# TH8_Supply.net
KiCad netlist of a schematic drawn in Altium Designer
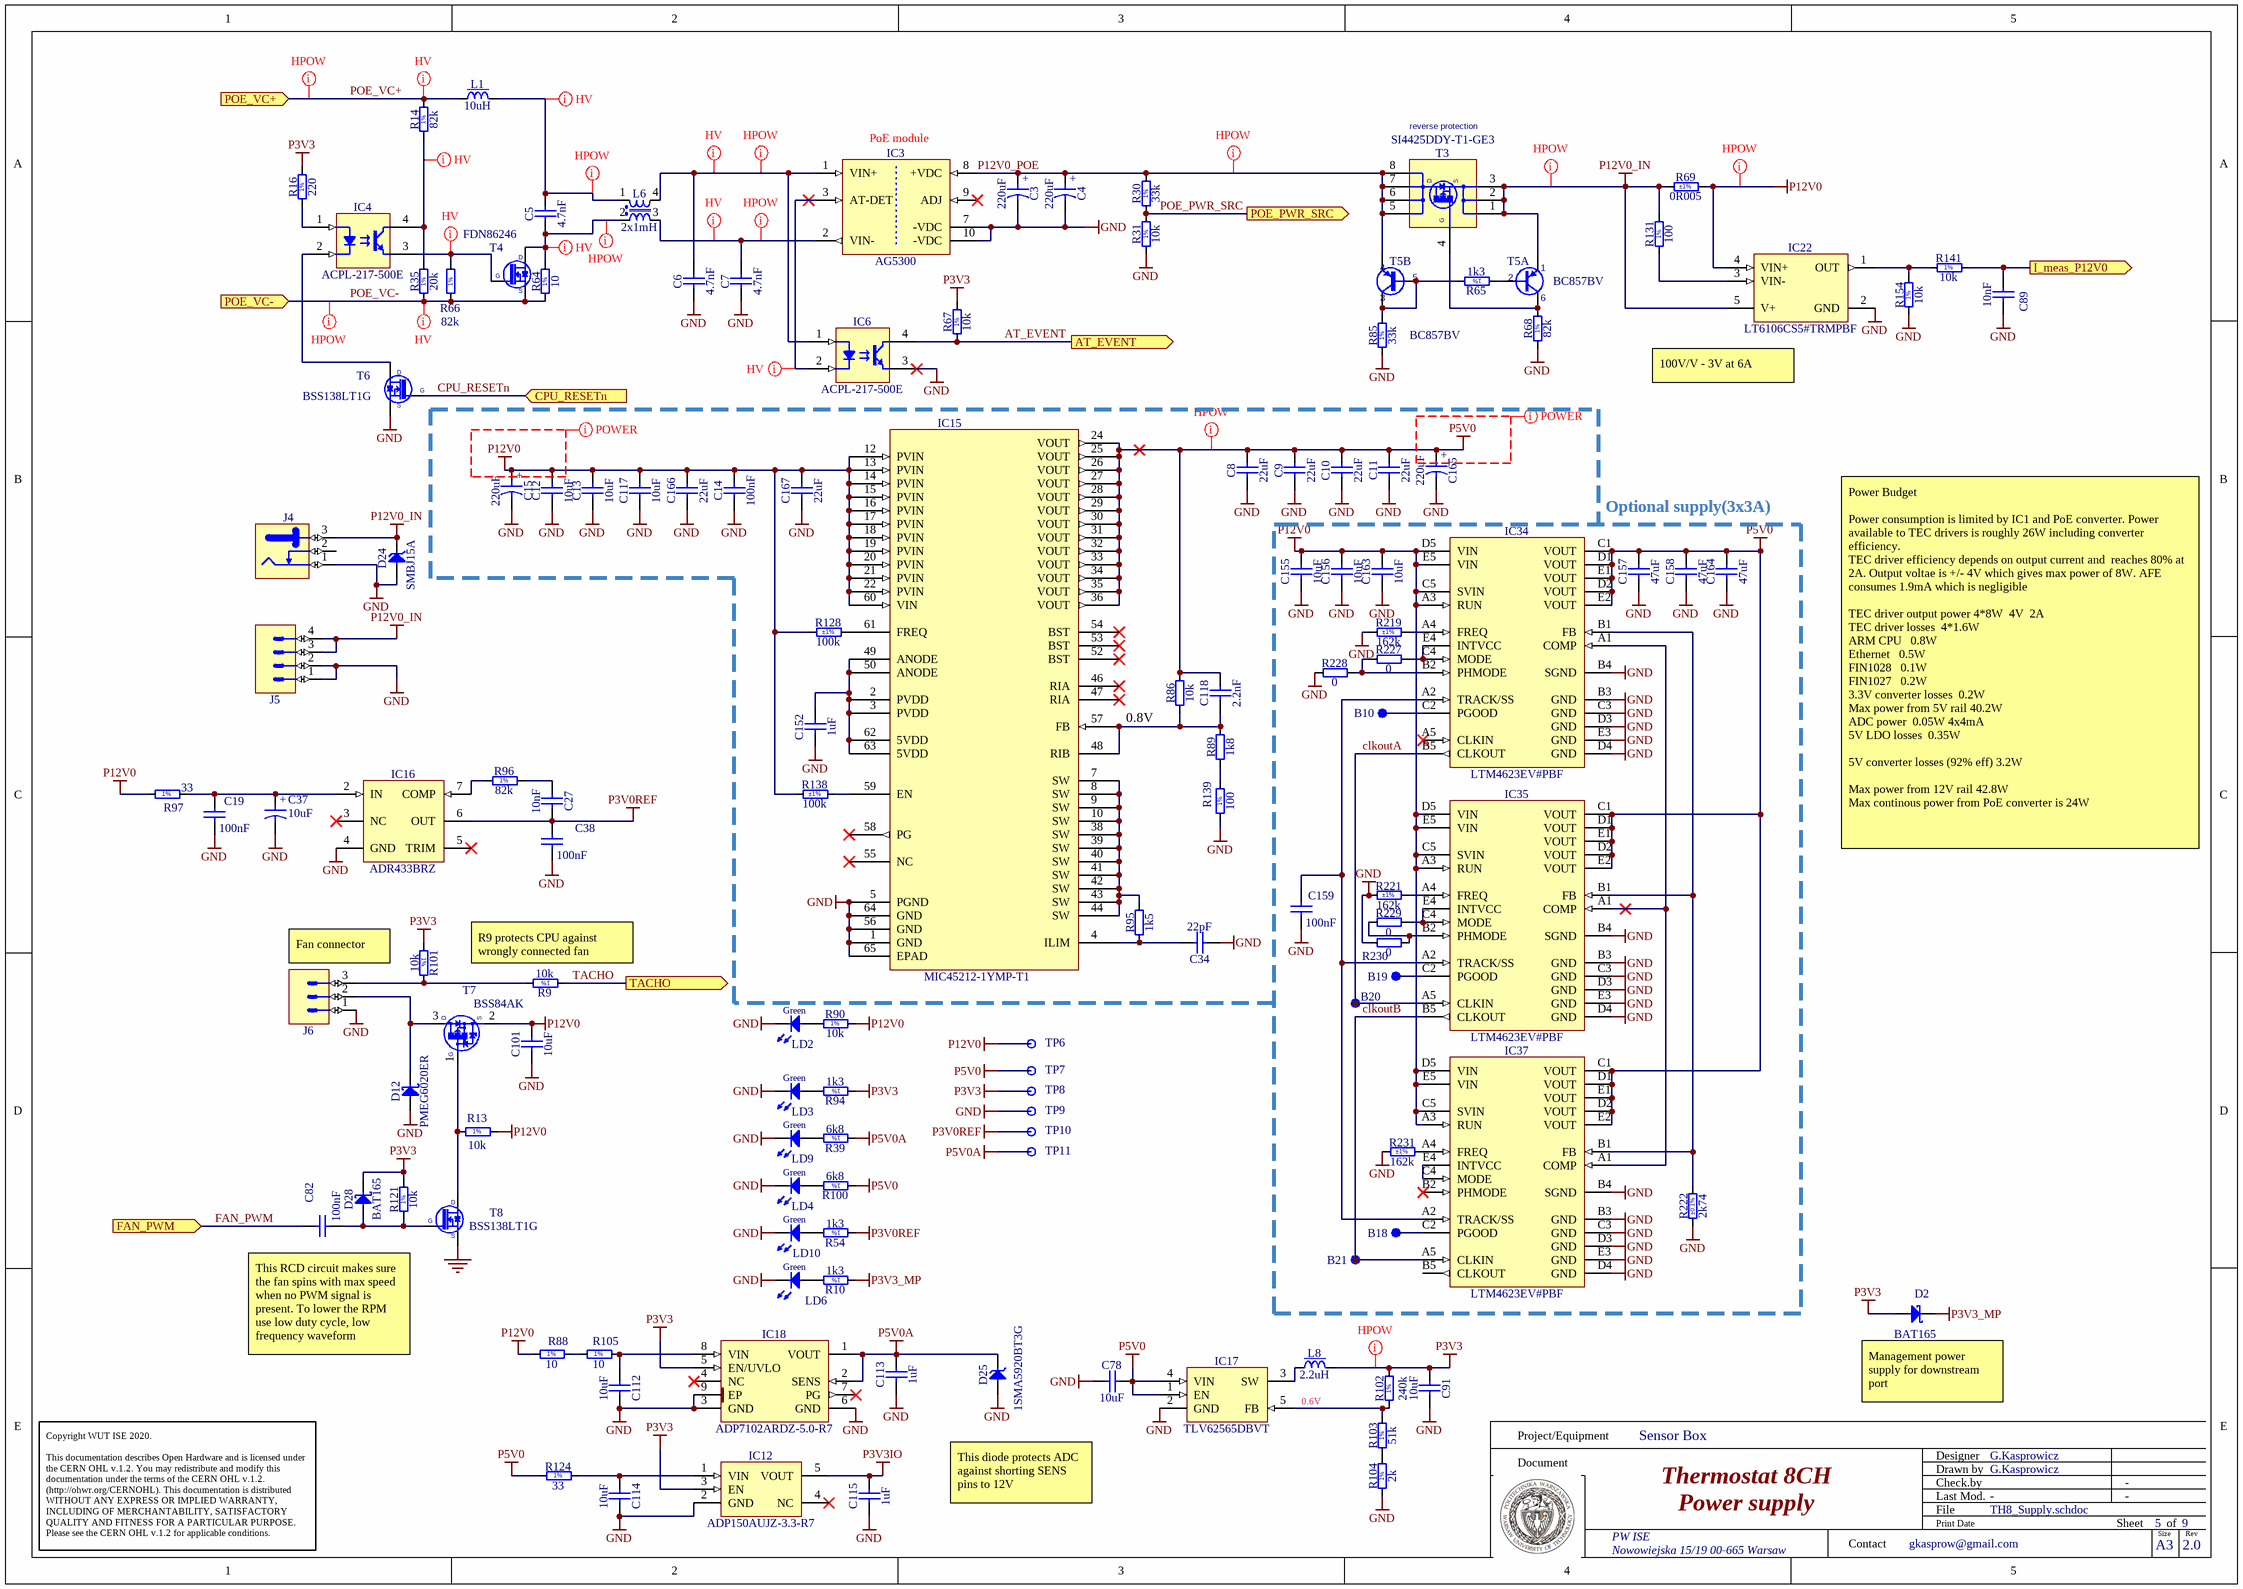
[diagram p0: TH8_Supply.schdoc]

(export (version "E")
  (design (tool "Eeschema 10.0.6"))
  (components
    (comp (ref "B10")
      (value "SMD Pad")
      (footprint "C75")
      (description "Through Hole Pad")
      (fields (field (name "PART NUMBER") "SMD_PAD_D0.75MM") (field (name "AUTHOR") "CERN DEM BC"))
      (libsource (lib "Eletro-mechanical") (part "Single SMD Pad (Round)"))
    )
    (comp (ref "B18")
      (value "SMD Pad")
      (footprint "C75")
      (description "Through Hole Pad")
      (fields (field (name "PART NUMBER") "SMD_PAD_D0.75MM") (field (name "AUTHOR") "CERN DEM BC"))
      (libsource (lib "Eletro-mechanical") (part "Single SMD Pad (Round)"))
    )
    (comp (ref "B19")
      (value "SMD Pad")
      (footprint "C75")
      (description "Through Hole Pad")
      (fields (field (name "PART NUMBER") "SMD_PAD_D0.75MM") (field (name "AUTHOR") "CERN DEM BC"))
      (libsource (lib "Eletro-mechanical") (part "Single SMD Pad (Round)"))
    )
    (comp (ref "B20")
      (value "SMD Pad")
      (footprint "C75")
      (description "Through Hole Pad")
      (fields (field (name "PART NUMBER") "SMD_PAD_D0.75MM") (field (name "AUTHOR") "CERN DEM BC"))
      (libsource (lib "Eletro-mechanical") (part "Single SMD Pad (Round)"))
    )
    (comp (ref "B21")
      (value "SMD Pad")
      (footprint "C75")
      (description "Through Hole Pad")
      (fields (field (name "PART NUMBER") "SMD_PAD_D0.75MM") (field (name "AUTHOR") "CERN DEM BC"))
      (libsource (lib "Eletro-mechanical") (part "Single SMD Pad (Round)"))
    )
    (comp (ref "C3")
      (value "220uF")
      (footprint "CAPMP7343X430N")
      (description "Polarised capacitor")
      (fields
        (field (name "PART NUMBER") "CTE7343-43_220UF_16V_10%")
        (field (name "VOLTAGE") "16V")
        (field (name "AUTHOR") "CERN DEM JLC")
      )
      (libsource (lib "Capacitors") (part "Capacitor - polarized"))
    )
    (comp (ref "C4")
      (value "220uF")
      (footprint "CAPMP7343X430N")
      (description "Polarised capacitor")
      (fields
        (field (name "PART NUMBER") "CTE7343-43_220UF_16V_10%")
        (field (name "VOLTAGE") "16V")
        (field (name "AUTHOR") "CERN DEM JLC")
      )
      (libsource (lib "Capacitors") (part "Capacitor - polarized"))
    )
    (comp (ref "C5")
      (value "4.7nF")
      (footprint "CAPC3216X140N")
      (description "Non-polarised capacitor")
      (fields
        (field (name "PART NUMBER") "CC1206_4.7NF_500V_10%_X7R")
        (field (name "VOLTAGE") "500V")
        (field (name "AUTHOR") "GK")
      )
      (libsource (lib "LIBRARY_SCH") (part "CAP_SMD_1206_4.7n_500V"))
    )
    (comp (ref "C6")
      (value "4.7nF")
      (footprint "CAPC3216X140N")
      (description "Non-polarised capacitor")
      (fields
        (field (name "PART NUMBER") "CC1206_4.7NF_500V_10%_X7R")
        (field (name "VOLTAGE") "500V")
        (field (name "AUTHOR") "GK")
      )
      (libsource (lib "LIBRARY_SCH") (part "CAP_SMD_1206_4.7n_500V"))
    )
    (comp (ref "C7")
      (value "4.7nF")
      (footprint "CAPC3216X140N")
      (description "Non-polarised capacitor")
      (fields
        (field (name "PART NUMBER") "CC1206_4.7NF_500V_10%_X7R")
        (field (name "VOLTAGE") "500V")
        (field (name "AUTHOR") "GK")
      )
      (libsource (lib "LIBRARY_SCH") (part "CAP_SMD_1206_4.7n_500V"))
    )
    (comp (ref "C8")
      (value "22uF")
      (footprint "CAPC2012X135N")
      (description "Non-polarised capacitor")
      (fields
        (field (name "PART NUMBER") "CC0805_22UF_16V_10%_X5R")
        (field (name "VOLTAGE") "16V")
        (field (name "AUTHOR") "CERN DEM JLC")
      )
      (libsource (lib "Capacitors") (part "Capacitor - non polarized"))
    )
    (comp (ref "C9")
      (value "22uF")
      (footprint "CAPC2012X135N")
      (description "Non-polarised capacitor")
      (fields
        (field (name "PART NUMBER") "CC0805_22UF_16V_10%_X5R")
        (field (name "VOLTAGE") "16V")
        (field (name "AUTHOR") "CERN DEM JLC")
      )
      (libsource (lib "Capacitors") (part "Capacitor - non polarized"))
    )
    (comp (ref "C10")
      (value "22uF")
      (footprint "CAPC2012X135N")
      (description "Non-polarised capacitor")
      (fields
        (field (name "PART NUMBER") "CC0805_22UF_16V_10%_X5R")
        (field (name "VOLTAGE") "16V")
        (field (name "AUTHOR") "CERN DEM JLC")
      )
      (libsource (lib "Capacitors") (part "Capacitor - non polarized"))
    )
    (comp (ref "C11")
      (value "22uF")
      (footprint "CAPC2012X135N")
      (description "Non-polarised capacitor")
      (fields
        (field (name "PART NUMBER") "CC0805_22UF_16V_10%_X5R")
        (field (name "VOLTAGE") "16V")
        (field (name "AUTHOR") "CERN DEM JLC")
      )
      (libsource (lib "Capacitors") (part "Capacitor - non polarized"))
    )
    (comp (ref "C12")
      (value "10uF")
      (footprint "CAPC2012X135N")
      (description "Non-polarised capacitor")
      (fields
        (field (name "PART NUMBER") "CC0805_10UF_16V_10%_X5R")
        (field (name "VOLTAGE") "16V")
        (field (name "AUTHOR") "CERN DEM JLC")
      )
      (libsource (lib "Capacitors") (part "Capacitor - non polarized"))
    )
    (comp (ref "C13")
      (value "10uF")
      (footprint "CAPC2012X135N")
      (description "Non-polarised capacitor")
      (fields
        (field (name "PART NUMBER") "CC0805_10UF_16V_10%_X5R")
        (field (name "VOLTAGE") "16V")
        (field (name "AUTHOR") "CERN DEM JLC")
      )
      (libsource (lib "Capacitors") (part "Capacitor - non polarized"))
    )
    (comp (ref "C14")
      (value "100nF")
      (footprint "CAPC1005X55N")
      (description "Non-polarised capacitor")
      (fields
        (field (name "PART NUMBER") "CC0402_100NF_16V_10%_X5R")
        (field (name "VOLTAGE") "16V")
        (field (name "AUTHOR") "CERN DEM JLC")
      )
      (libsource (lib "Capacitors") (part "Capacitor - non polarized"))
    )
    (comp (ref "C15")
      (value "220uF")
      (footprint "CAPMP7343X430N")
      (description "Polarised capacitor")
      (fields
        (field (name "PART NUMBER") "CTE7343-43_220UF_16V_10%")
        (field (name "VOLTAGE") "16V")
        (field (name "AUTHOR") "CERN DEM JLC")
      )
      (libsource (lib "Capacitors") (part "Capacitor - polarized"))
    )
    (comp (ref "C19")
      (value "100nF")
      (footprint "CAPC1005X55N")
      (description "Non-polarised capacitor")
      (fields
        (field (name "PART NUMBER") "CC0402_100NF_16V_10%_X5R")
        (field (name "VOLTAGE") "16V")
        (field (name "AUTHOR") "CERN DEM JLC")
      )
      (libsource (lib "Capacitors") (part "Capacitor - non polarized"))
    )
    (comp (ref "C27")
      (value "10nF")
      (footprint "CAPC1005X55N")
      (description "Non-polarised capacitor")
      (fields
        (field (name "PART NUMBER") "CC0402_10NF_16V_10%_X7R")
        (field (name "VOLTAGE") "16V")
        (field (name "AUTHOR") "CERN DEM JLC")
      )
      (libsource (lib "Capacitors") (part "Capacitor - non polarized"))
    )
    (comp (ref "C34")
      (value "22pF")
      (footprint "CAPC1005X55N")
      (description "Non-polarised capacitor")
      (fields
        (field (name "PART NUMBER") "CC0402_22PF_50V_5%_C0G")
        (field (name "VOLTAGE") "50V")
        (field (name "AUTHOR") "CERN DEM JLC")
      )
      (libsource (lib "Capacitors") (part "Capacitor - non polarized"))
    )
    (comp (ref "C37")
      (value "10uF")
      (footprint "CAPMP3216X180N")
      (description "Polarised capacitor")
      (fields
        (field (name "PART NUMBER") "CTE3216-18_10UF_16V_20%_AVX_TCJ")
        (field (name "VOLTAGE") "16V")
        (field (name "AUTHOR") "CERN DEM JLC")
      )
      (libsource (lib "Capacitors") (part "Capacitor - polarized"))
    )
    (comp (ref "C38")
      (value "100nF")
      (footprint "CAPC1005X55N")
      (description "Non-polarised capacitor")
      (fields
        (field (name "PART NUMBER") "CC0402_100NF_16V_10%_X5R")
        (field (name "VOLTAGE") "16V")
        (field (name "AUTHOR") "CERN DEM JLC")
      )
      (libsource (lib "Capacitors") (part "Capacitor - non polarized"))
    )
    (comp (ref "C78")
      (value "10uF")
      (footprint "CAPC2012X135N")
      (description "Non-polarised capacitor")
      (fields
        (field (name "PART NUMBER") "CC0805_10UF_16V_10%_X5R")
        (field (name "VOLTAGE") "16V")
        (field (name "AUTHOR") "CERN DEM JLC")
      )
      (libsource (lib "Capacitors") (part "Capacitor - non polarized"))
    )
    (comp (ref "C82")
      (value "100nF")
      (footprint "CAPC1005X55N")
      (description "Non-polarised capacitor")
      (fields
        (field (name "PART NUMBER") "CC0402_100NF_16V_10%_X5R")
        (field (name "VOLTAGE") "16V")
        (field (name "AUTHOR") "CERN DEM JLC")
      )
      (libsource (lib "Capacitors") (part "Capacitor - non polarized"))
    )
    (comp (ref "C89")
      (value "10nF")
      (footprint "CAPC1005X55N")
      (description "Non-polarised capacitor")
      (fields
        (field (name "PART NUMBER") "CC0402_10NF_25V_10%_X7R")
        (field (name "VOLTAGE") "25V")
        (field (name "AUTHOR") "CERN DEM JLC")
      )
      (libsource (lib "Capacitors") (part "Capacitor - non polarized"))
    )
    (comp (ref "C91")
      (value "10uF")
      (footprint "CAPC2012X135N")
      (description "Non-polarised capacitor")
      (fields
        (field (name "PART NUMBER") "CC0805_10UF_16V_10%_X5R")
        (field (name "VOLTAGE") "16V")
        (field (name "AUTHOR") "CERN DEM JLC")
      )
      (libsource (lib "Capacitors") (part "Capacitor - non polarized"))
    )
    (comp (ref "C101")
      (value "10uF")
      (footprint "CAPC2012X135N")
      (description "Non-polarised capacitor")
      (fields
        (field (name "PART NUMBER") "CC0805_10UF_16V_10%_X5R")
        (field (name "VOLTAGE") "16V")
        (field (name "AUTHOR") "CERN DEM JLC")
      )
      (libsource (lib "Capacitors") (part "Capacitor - non polarized"))
    )
    (comp (ref "C112")
      (value "10uF")
      (footprint "CAPC2012X135N")
      (description "Non-polarised capacitor")
      (fields
        (field (name "PART NUMBER") "CC0805_10UF_16V_10%_X5R")
        (field (name "VOLTAGE") "16V")
        (field (name "AUTHOR") "CERN DEM JLC")
      )
      (libsource (lib "Capacitors") (part "Capacitor - non polarized"))
    )
    (comp (ref "C113")
      (value "1uF")
      (footprint "CAPC1608X87N")
      (description "Non-polarised capacitor")
      (fields
        (field (name "PART NUMBER") "CC0603_1UF_25V_10%_X7R")
        (field (name "VOLTAGE") "25V")
        (field (name "AUTHOR") "CERN DEM JLC")
      )
      (libsource (lib "Capacitors") (part "Capacitor - non polarized"))
    )
    (comp (ref "C114")
      (value "10uF")
      (footprint "CAPC2012X135N")
      (description "Non-polarised capacitor")
      (fields
        (field (name "PART NUMBER") "CC0805_10UF_16V_10%_X5R")
        (field (name "VOLTAGE") "16V")
        (field (name "AUTHOR") "CERN DEM JLC")
      )
      (libsource (lib "Capacitors") (part "Capacitor - non polarized"))
    )
    (comp (ref "C115")
      (value "1uF")
      (footprint "CAPC1608X87N")
      (description "Non-polarised capacitor")
      (fields
        (field (name "PART NUMBER") "CC0603_1UF_25V_10%_X7R")
        (field (name "VOLTAGE") "25V")
        (field (name "AUTHOR") "CERN DEM JLC")
      )
      (libsource (lib "Capacitors") (part "Capacitor - non polarized"))
    )
    (comp (ref "C117")
      (value "10uF")
      (footprint "CAPC2012X135N")
      (description "Non-polarised capacitor")
      (fields
        (field (name "PART NUMBER") "CC0805_10UF_16V_10%_X5R")
        (field (name "VOLTAGE") "16V")
        (field (name "AUTHOR") "CERN DEM JLC")
      )
      (libsource (lib "Capacitors") (part "Capacitor - non polarized"))
    )
    (comp (ref "C118")
      (value "2.2nF")
      (footprint "CAPC1608X87N")
      (description "Non-polarised capacitor")
      (fields
        (field (name "PART NUMBER") "CC0603_2.2NF_50V_5%_C0G")
        (field (name "VOLTAGE") "50V")
        (field (name "AUTHOR") "CERN DEM JMW")
      )
      (libsource (lib "Capacitors") (part "Capacitor - non polarized"))
    )
    (comp (ref "C152")
      (value "1uF")
      (footprint "CAPC1608X87N")
      (description "Non-polarised capacitor")
      (fields
        (field (name "PART NUMBER") "CC0603_1UF_25V_10%_X7R")
        (field (name "VOLTAGE") "25V")
        (field (name "AUTHOR") "CERN DEM JLC")
      )
      (libsource (lib "Capacitors") (part "Capacitor - non polarized"))
    )
    (comp (ref "C155")
      (value "10uF")
      (footprint "CAPC2012X135N")
      (description "Non-polarised capacitor")
      (fields
        (field (name "PART NUMBER") "CC0805_10UF_16V_10%_X5R")
        (field (name "VOLTAGE") "16V")
        (field (name "AUTHOR") "CERN DEM JLC")
      )
      (libsource (lib "Capacitors") (part "Capacitor - non polarized"))
    )
    (comp (ref "C156")
      (value "10uF")
      (footprint "CAPC2012X135N")
      (description "Non-polarised capacitor")
      (fields
        (field (name "PART NUMBER") "CC0805_10UF_16V_10%_X5R")
        (field (name "VOLTAGE") "16V")
        (field (name "AUTHOR") "CERN DEM JLC")
      )
      (libsource (lib "Capacitors") (part "Capacitor - non polarized"))
    )
    (comp (ref "C157")
      (value "47uF")
      (footprint "CAPC2012X145N")
      (description "Non-polarised capacitor")
      (fields
        (field (name "PART NUMBER") "CC0805_47UF_10V_20%_X5R")
        (field (name "VOLTAGE") "10V")
        (field (name "AUTHOR") "CERN DEM BC")
      )
      (libsource (lib "Capacitors") (part "Capacitor - non polarized"))
    )
    (comp (ref "C158")
      (value "47uF")
      (footprint "CAPC2012X145N")
      (description "Non-polarised capacitor")
      (fields
        (field (name "PART NUMBER") "CC0805_47UF_10V_20%_X5R")
        (field (name "VOLTAGE") "10V")
        (field (name "AUTHOR") "CERN DEM BC")
      )
      (libsource (lib "Capacitors") (part "Capacitor - non polarized"))
    )
    (comp (ref "C159")
      (value "100nF")
      (footprint "CAPC1005X55N")
      (description "Non-polarised capacitor")
      (fields
        (field (name "PART NUMBER") "CC0402_100NF_16V_10%_X5R")
        (field (name "VOLTAGE") "16V")
        (field (name "AUTHOR") "CERN DEM JLC")
      )
      (libsource (lib "Capacitors") (part "Capacitor - non polarized"))
    )
    (comp (ref "C163")
      (value "10uF")
      (footprint "CAPC2012X135N")
      (description "Non-polarised capacitor")
      (fields
        (field (name "PART NUMBER") "CC0805_10UF_16V_10%_X5R")
        (field (name "VOLTAGE") "16V")
        (field (name "AUTHOR") "CERN DEM JLC")
      )
      (libsource (lib "Capacitors") (part "Capacitor - non polarized"))
    )
    (comp (ref "C164")
      (value "47uF")
      (footprint "CAPC2012X145N")
      (description "Non-polarised capacitor")
      (fields
        (field (name "PART NUMBER") "CC0805_47UF_10V_20%_X5R")
        (field (name "VOLTAGE") "10V")
        (field (name "AUTHOR") "CERN DEM BC")
      )
      (libsource (lib "Capacitors") (part "Capacitor - non polarized"))
    )
    (comp (ref "C165")
      (value "220uF")
      (footprint "CAPMP7343X430N")
      (description "Polarised capacitor")
      (fields
        (field (name "PART NUMBER") "CTE7343-43_220UF_16V_10%")
        (field (name "VOLTAGE") "16V")
        (field (name "AUTHOR") "CERN DEM JLC")
      )
      (libsource (lib "Capacitors") (part "Capacitor - polarized"))
    )
    (comp (ref "C166")
      (value "22uF")
      (footprint "CAPC2012X135N")
      (description "Non-polarised capacitor")
      (fields
        (field (name "PART NUMBER") "CC0805_22UF_16V_10%_X5R")
        (field (name "VOLTAGE") "16V")
        (field (name "AUTHOR") "CERN DEM JLC")
      )
      (libsource (lib "Capacitors") (part "Capacitor - non polarized"))
    )
    (comp (ref "C167")
      (value "22uF")
      (footprint "CAPC2012X135N")
      (description "Non-polarised capacitor")
      (fields
        (field (name "PART NUMBER") "CC0805_22UF_16V_10%_X5R")
        (field (name "VOLTAGE") "16V")
        (field (name "AUTHOR") "CERN DEM JLC")
      )
      (libsource (lib "Capacitors") (part "Capacitor - non polarized"))
    )
    (comp (ref "D2")
      (value "BAT165")
      (footprint "SOD2512X110N")
      (description "Schottky Diode")
      (fields
        (field (name "VOLTAGE") "40V")
        (field (name "POWER") "750mA")
        (field (name "AUTHOR") "CERN DEM JLC")
      )
      (libsource (lib "ICs And Semiconductors") (part "Diode Schottky"))
    )
    (comp (ref "D12")
      (value "PMEG6020ER")
      (footprint "SODFL3517X110N")
      (description "Schottky Diode")
      (fields
        (field (name "VOLTAGE") "60V")
        (field (name "POWER") "2A")
        (field (name "AUTHOR") "CERN DEM JMW")
      )
      (libsource (lib "ICs And Semiconductors") (part "Diode Schottky"))
    )
    (comp (ref "D24")
      (value "SMBJ15A")
      (footprint "DIOM5336X265N")
      (description "Zener Diode")
      (fields
        (field (name "VOLTAGE") "15V")
        (field (name "POWER") "600W")
        (field (name "AUTHOR") "CERN DEM JLC")
      )
      (libsource (lib "ICs And Semiconductors") (part "Diode Zener"))
    )
    (comp (ref "D25")
      (value "1SMA5920BT3G")
      (footprint "DIOM5226X220N")
      (description "6.2V 1.5 Watt Plastic Surface Mount Zener Voltage Regulators")
      (fields (field (name "VOLTAGE") "6.2V") (field (name "POWER") "1.5W") (field (name "AUTHOR") "GK"))
      (libsource (lib "Diodes") (part "D_Zener_1SMA5920BT3G"))
    )
    (comp (ref "D28")
      (value "BAT165")
      (footprint "SOD2512X110N")
      (description "Schottky Diode")
      (fields
        (field (name "VOLTAGE") "40V")
        (field (name "POWER") "750mA")
        (field (name "AUTHOR") "CERN DEM JLC")
      )
      (libsource (lib "ICs And Semiconductors") (part "Diode Schottky"))
    )
    (comp (ref "IC3")
      (value "AG5300")
      (footprint "SILVERTEL_AG5300")
      (description "Power-over-Ethernet Plus (POE+) Module")
      (fields (field (name "MANUFACTURER") "SILVERTEL") (field (name "AUTHOR") "CERN DEM JLC"))
      (libsource (lib "ICs And Semiconductors") (part "AG5300"))
    )
    (comp (ref "IC4")
      (value "ACPL-217-500E")
      (footprint "SOIC127P700X242-4N")
      (description "Single Optocoupler")
      (fields (field (name "MANUFACTURER") "AVAGO TECHNOLOGIES") (field (name "AUTHOR") "CERN DEM JLC"))
      (libsource (lib "ICs And Semiconductors") (part "Optocoupler Type7"))
    )
    (comp (ref "IC6")
      (value "ACPL-217-500E")
      (footprint "SOIC127P700X242-4N")
      (description "Single Optocoupler")
      (fields (field (name "MANUFACTURER") "AVAGO TECHNOLOGIES") (field (name "AUTHOR") "CERN DEM JLC"))
      (libsource (lib "ICs And Semiconductors") (part "Optocoupler Type7"))
    )
    (comp (ref "IC12")
      (value "ADP150AUJZ-3.3-R7")
      (footprint "SOT95P280X90-5N")
      (description "Ultralow Noise, 150 mA CMOS Linear Regulator")
      (fields (field (name "MANUFACTURER") "ANALOG DEVICES") (field (name "AUTHOR") "CERN DEM JLC"))
      (libsource (lib "ICs And Semiconductors") (part "ADP150AUJZ"))
    )
    (comp (ref "IC15")
      (value "MIC45212-1YMP-T1")
      (footprint "MICROCHIP_QFN64_12X12")
      (description "0.8V to 85% PVIN (4.5...26V), 14A Synchronous Step-Down Regulator Module")
      (fields (field (name "MANUFACTURER") "MICROCHIP TECHNOLOGY") (field (name "AUTHOR") "GK"))
      (libsource (lib "Regulators_SMPS") (part "PM_MIC45212-1"))
    )
    (comp (ref "IC16")
      (value "ADR433BRZ")
      (footprint "SOIC127P600X175-8N")
      (fields (field (name "MANUFACTURER") "ANALOG DEVICES") (field (name "AUTHOR") "CERN DEM JMW"))
      (libsource (lib "ICs And Semiconductors") (part "ADR433"))
    )
    (comp (ref "IC17")
      (value "TLV62565DBVT")
      (footprint "SOT95P280X145-5N")
      (description "1.5A High Efficiency Step-Down Converter, Adjustable Output Voltage")
      (fields (field (name "MANUFACTURER") "TEXAS INSTRUMENTS") (field (name "AUTHOR") "CERN DEM JMW"))
      (libsource (lib "ICs And Semiconductors") (part "TLV62565"))
    )
    (comp (ref "IC18")
      (value "ADP7102ARDZ-5.0-R7")
      (footprint "SOIC127P600X175-9N-R241X309")
      (description "300 mA, Low Noise, CMOS LDO Linear Regulator")
      (fields (field (name "MANUFACTURER") "ANALOG DEVICES") (field (name "AUTHOR") "CERN DEM JLC"))
      (libsource (lib "ICs And Semiconductors") (part "ADP7102ARDZ-X.X-R7"))
    )
    (comp (ref "IC22")
      (value "LT6106CS5#TRMPBF")
      (footprint "SOT95P280X145-5N")
      (description "Current Shunt Monitor -16V to +80V Common-Mode Range")
      (fields (field (name "MANUFACTURER") "ANALOG DEVICES") (field (name "AUTHOR") "GK"))
      (libsource (lib "ICs_Analog_Interfaces") (part "AMP_LT6106"))
    )
    (comp (ref "IC34")
      (value "LTM4623EV#PBF")
      (footprint "LGA25C127P5X5_625X625X192")
      (description "4V-20V to 0.6V-5.5V, Iout 3A Step-Down DC/DC uModule Regulator")
      (fields (field (name "MANUFACTURER") "LINEAR TECHNOLOGY") (field (name "AUTHOR") "CERN DEM JMW"))
      (libsource (lib "ICs And Semiconductors") (part "LTM4623"))
    )
    (comp (ref "IC35")
      (value "LTM4623EV#PBF")
      (footprint "LGA25C127P5X5_625X625X192")
      (description "4V-20V to 0.6V-5.5V, Iout 3A Step-Down DC/DC uModule Regulator")
      (fields (field (name "MANUFACTURER") "LINEAR TECHNOLOGY") (field (name "AUTHOR") "CERN DEM JMW"))
      (libsource (lib "ICs And Semiconductors") (part "LTM4623"))
    )
    (comp (ref "IC37")
      (value "LTM4623EV#PBF")
      (footprint "LGA25C127P5X5_625X625X192")
      (description "4V-20V to 0.6V-5.5V, Iout 3A Step-Down DC/DC uModule Regulator")
      (fields (field (name "MANUFACTURER") "LINEAR TECHNOLOGY") (field (name "AUTHOR") "CERN DEM JMW"))
      (libsource (lib "ICs And Semiconductors") (part "LTM4623"))
    )
    (comp (ref "J4")
      (value "Jack")
      (footprint "SWITCHCRAFT_L712RA")
      (description "24V /3. 5A, 2.1mm Diameter Pin, SMD DC Power Supply Connector With  Break Contact")
      (fields
        (field (name "PART NUMBER") "SWITCHCRAFT_712RA")
        (field (name "MANUFACTURER") "SWITCHCRAFT")
        (field (name "AUTHOR") "GK")
      )
      (libsource (lib "LIBRARY_SCH") (part "CON_DC_5A_THT_RA"))
    )
    (comp (ref "J5")
      (value "Mini-Fit Jr.™")
      (footprint "MOLEX_39-30-0040")
      (description "Connector 4 Male")
      (fields
        (field (name "PART NUMBER") "MOLEX_39-30-0040")
        (field (name "MANUFACTURER") "MOLEX")
        (field (name "AUTHOR") "CERN DEM JLC")
      )
      (libsource (lib "Connectors") (part "Connector 4 Male"))
    )
    (comp (ref "J6")
      (value "KK®")
      (footprint "MOLEX_22-27-2031")
      (description "Connector 3 Male")
      (fields
        (field (name "PART NUMBER") "MOLEX_22-27-2031")
        (field (name "MANUFACTURER") "MOLEX")
        (field (name "AUTHOR") "CERN DEM JLC")
      )
      (libsource (lib "Connectors") (part "Connector 3 Male"))
    )
    (comp (ref "L1")
      (value "10uH")
      (footprint "IND_MURATA-PS_8400")
      (description "Inductor With Core")
      (fields
        (field (name "PART NUMBER") "IND_10UH_10%_MURATA-PS_8400")
        (field (name "POWER") "950mA")
        (field (name "AUTHOR") "CERN DEM JLC")
      )
      (libsource (lib "Inductors & Transformers") (part "Inductor With Magnetic core"))
    )
    (comp (ref "L6")
      (value "2x1mH")
      (footprint "IND_WURTH_WE-SL2")
      (description "Inductor Common Mode")
      (fields
        (field (name "PART NUMBER") "IND_1MH_50%_WURTH_WE-SL2-744222")
        (field (name "POWER") "800mA")
        (field (name "AUTHOR") "CERN DEM JLC")
      )
      (libsource (lib "Inductors & Transformers") (part "Inductor Common Mode 1Dot-4 2Dot-3"))
    )
    (comp (ref "L8")
      (value "2.2uH")
      (footprint "IND_MURATA_LQH44PN_P0")
      (description "Inductor With Core")
      (fields
        (field (name "PART NUMBER") "IND_2.2UH_20%_MURATA_LQH44PN2R2MP0L")
        (field (name "POWER") "1.8A")
        (field (name "AUTHOR") "CERN DEM JLC")
      )
      (libsource (lib "Inductors & Transformers") (part "Inductor With Magnetic core"))
    )
    (comp (ref "LD2")
      (value "Green")
      (footprint "LED_KINGBRIGHT_KPH-1608CGCK")
      (description "LED Green 1C 2A")
      (fields
        (field (name "PART NUMBER") "LED_KINGBRIGHT_KPH-1608CGCK")
        (field (name "MANUFACTURER") "KINGBRIGHT")
        (field (name "AUTHOR") "CERN DEM JLC")
      )
      (libsource (lib "ICs And Semiconductors") (part "LED Green 1C 2A"))
    )
    (comp (ref "LD3")
      (value "Green")
      (footprint "LED_KINGBRIGHT_KPH-1608CGCK")
      (description "LED Green 1C 2A")
      (fields
        (field (name "PART NUMBER") "LED_KINGBRIGHT_KPH-1608CGCK")
        (field (name "MANUFACTURER") "KINGBRIGHT")
        (field (name "AUTHOR") "CERN DEM JLC")
      )
      (libsource (lib "ICs And Semiconductors") (part "LED Green 1C 2A"))
    )
    (comp (ref "LD4")
      (value "Green")
      (footprint "LED_KINGBRIGHT_KPH-1608CGCK")
      (description "LED Green 1C 2A")
      (fields
        (field (name "PART NUMBER") "LED_KINGBRIGHT_KPH-1608CGCK")
        (field (name "MANUFACTURER") "KINGBRIGHT")
        (field (name "AUTHOR") "CERN DEM JLC")
      )
      (libsource (lib "ICs And Semiconductors") (part "LED Green 1C 2A"))
    )
    (comp (ref "LD6")
      (value "Green")
      (footprint "LED_KINGBRIGHT_KPH-1608CGCK")
      (description "LED Green 1C 2A")
      (fields
        (field (name "PART NUMBER") "LED_KINGBRIGHT_KPH-1608CGCK")
        (field (name "MANUFACTURER") "KINGBRIGHT")
        (field (name "AUTHOR") "CERN DEM JLC")
      )
      (libsource (lib "ICs And Semiconductors") (part "LED Green 1C 2A"))
    )
    (comp (ref "LD9")
      (value "Green")
      (footprint "LED_KINGBRIGHT_KPH-1608CGCK")
      (description "LED Green 1C 2A")
      (fields
        (field (name "PART NUMBER") "LED_KINGBRIGHT_KPH-1608CGCK")
        (field (name "MANUFACTURER") "KINGBRIGHT")
        (field (name "AUTHOR") "CERN DEM JLC")
      )
      (libsource (lib "ICs And Semiconductors") (part "LED Green 1C 2A"))
    )
    (comp (ref "LD10")
      (value "Green")
      (footprint "LED_KINGBRIGHT_KPH-1608CGCK")
      (description "LED Green 1C 2A")
      (fields
        (field (name "PART NUMBER") "LED_KINGBRIGHT_KPH-1608CGCK")
        (field (name "MANUFACTURER") "KINGBRIGHT")
        (field (name "AUTHOR") "CERN DEM JLC")
      )
      (libsource (lib "ICs And Semiconductors") (part "LED Green 1C 2A"))
    )
    (comp (ref "R9")
      (value "10k")
      (footprint "RESC1005X40N")
      (description "Resistor - 1%")
      (fields
        (field (name "PART NUMBER") "R0402_10K_1%_0.0625W_100PPM")
        (field (name "POWER") "0.0625W")
        (field (name "AUTHOR") "CERN DEM JLC")
      )
      (libsource (lib "Resistors") (part "Resistor - 1%"))
    )
    (comp (ref "R10")
      (value "1k3")
      (footprint "RESC1608X55N")
      (description "Resistor - 1%")
      (fields
        (field (name "PART NUMBER") "R0603_1K3_1%_0.1W_100PPM")
        (field (name "POWER") "0.1W")
        (field (name "AUTHOR") "CERN DEM JLC")
      )
      (libsource (lib "Resistors") (part "Resistor - 1%"))
    )
    (comp (ref "R13")
      (value "10k")
      (footprint "RESC1005X40N")
      (description "Resistor - 1%")
      (fields
        (field (name "PART NUMBER") "R0402_10K_1%_0.0625W_100PPM")
        (field (name "POWER") "0.0625W")
        (field (name "AUTHOR") "CERN DEM JLC")
      )
      (libsource (lib "Resistors") (part "Resistor - 1%"))
    )
    (comp (ref "R14")
      (value "82k")
      (footprint "RESC1608X55N")
      (description "Resistor - 1%")
      (fields
        (field (name "PART NUMBER") "R0603_82K_1%_0.1W_100PPM")
        (field (name "POWER") "0.1W")
        (field (name "AUTHOR") "CERN DEM JLC")
      )
      (libsource (lib "Resistors") (part "Resistor - 1%"))
    )
    (comp (ref "R16")
      (value "220")
      (footprint "RESC1608X55N")
      (description "Resistor - 1%")
      (fields
        (field (name "PART NUMBER") "R0603_220R_1%_0.1W_100PPM")
        (field (name "POWER") "0.1W")
        (field (name "AUTHOR") "CERN DEM JLC")
      )
      (libsource (lib "Resistors") (part "Resistor - 1%"))
    )
    (comp (ref "R30")
      (value "33k")
      (footprint "RESC1005X40N")
      (description "Resistor - 1%")
      (fields
        (field (name "PART NUMBER") "R0402_33K_1%_0.0625W_100PPM")
        (field (name "POWER") "0.0625W")
        (field (name "AUTHOR") "CERN DEM JLC")
      )
      (libsource (lib "Resistors") (part "Resistor - 1%"))
    )
    (comp (ref "R31")
      (value "10k")
      (footprint "RESC1005X40N")
      (description "Resistor - 1%")
      (fields
        (field (name "PART NUMBER") "R0402_10K_1%_0.0625W_100PPM")
        (field (name "POWER") "0.0625W")
        (field (name "AUTHOR") "CERN DEM JLC")
      )
      (libsource (lib "Resistors") (part "Resistor - 1%"))
    )
    (comp (ref "R35")
      (value "20k")
      (footprint "RESC1005X40N")
      (description "Resistor - 1%")
      (fields
        (field (name "PART NUMBER") "R0402_20K_1%_0.0625W_100PPM")
        (field (name "POWER") "0.0625W")
        (field (name "AUTHOR") "CERN DEM JLC")
      )
      (libsource (lib "Resistors") (part "Resistor - 1%"))
    )
    (comp (ref "R39")
      (value "6k8")
      (footprint "RESC1005X40N")
      (description "Resistor - 1%")
      (fields
        (field (name "PART NUMBER") "R0402_6K8_1%_0.0625W_100PPM")
        (field (name "POWER") "0.0625W")
        (field (name "AUTHOR") "CERN DEM JLC")
      )
      (libsource (lib "Resistors") (part "Resistor - 1%"))
    )
    (comp (ref "R54")
      (value "1k3")
      (footprint "RESC1608X55N")
      (description "Resistor - 1%")
      (fields
        (field (name "PART NUMBER") "R0603_1K3_1%_0.1W_100PPM")
        (field (name "POWER") "0.1W")
        (field (name "AUTHOR") "CERN DEM JLC")
      )
      (libsource (lib "Resistors") (part "Resistor - 1%"))
    )
    (comp (ref "R64")
      (value "10")
      (footprint "RESC2012X60N")
      (description "Resistor - 1%")
      (fields
        (field (name "PART NUMBER") "R0805_10R_1%_0.125W_200PPM")
        (field (name "POWER") "0.125W")
        (field (name "AUTHOR") "CERN DEM JLC")
      )
      (libsource (lib "Resistors") (part "Resistor - 1%"))
    )
    (comp (ref "R65")
      (value "1k3")
      (footprint "RESC1608X55N")
      (description "Resistor - 1%")
      (fields
        (field (name "PART NUMBER") "R0603_1K3_1%_0.1W_100PPM")
        (field (name "POWER") "0.1W")
        (field (name "AUTHOR") "CERN DEM JLC")
      )
      (libsource (lib "Resistors") (part "Resistor - 1%"))
    )
    (comp (ref "R66")
      (value "82k")
      (footprint "RESC1608X55N")
      (description "Resistor - 1%")
      (fields
        (field (name "PART NUMBER") "R0603_82K_1%_0.1W_100PPM")
        (field (name "POWER") "0.1W")
        (field (name "AUTHOR") "CERN DEM JLC")
      )
      (libsource (lib "Resistors") (part "Resistor - 1%"))
    )
    (comp (ref "R67")
      (value "10k")
      (footprint "RESC1005X40N")
      (description "Resistor - 1%")
      (fields
        (field (name "PART NUMBER") "R0402_10K_1%_0.0625W_100PPM")
        (field (name "POWER") "0.0625W")
        (field (name "AUTHOR") "CERN DEM JLC")
      )
      (libsource (lib "Resistors") (part "Resistor - 1%"))
    )
    (comp (ref "R68")
      (value "82k")
      (footprint "RESC1608X55N")
      (description "Resistor - 1%")
      (fields
        (field (name "PART NUMBER") "R0603_82K_1%_0.1W_100PPM")
        (field (name "POWER") "0.1W")
        (field (name "AUTHOR") "CERN DEM JLC")
      )
      (libsource (lib "Resistors") (part "Resistor - 1%"))
    )
    (comp (ref "R69")
      (value "0R005")
      (footprint "RESC3216X80N")
      (description "Resistor - 1%")
      (fields
        (field (name "TOLERANCE") "±1%")
        (field (name "PART NUMBER") "R1206_0R005_1%_1W_100PPM_TT_LRMAM1206")
        (field (name "POWER") "1W")
        (field (name "AUTHOR") "CERN DEM BC")
      )
      (libsource (lib "") (part "Resistor - 1%_1"))
    )
    (comp (ref "R85")
      (value "33k")
      (footprint "RESC1005X40N")
      (description "Resistor - 1%")
      (fields
        (field (name "PART NUMBER") "R0402_33K_1%_0.0625W_100PPM")
        (field (name "POWER") "0.0625W")
        (field (name "AUTHOR") "CERN DEM JLC")
      )
      (libsource (lib "Resistors") (part "Resistor - 1%"))
    )
    (comp (ref "R86")
      (value "10k")
      (footprint "RESC1005X40N")
      (description "Resistor - 1%")
      (fields
        (field (name "PART NUMBER") "R0402_10K_1%_0.0625W_100PPM")
        (field (name "POWER") "0.0625W")
        (field (name "AUTHOR") "CERN DEM JLC")
      )
      (libsource (lib "Resistors") (part "Resistor - 1%"))
    )
    (comp (ref "R88")
      (value "10")
      (footprint "RESC2012X60N")
      (description "Resistor - 1%")
      (fields
        (field (name "PART NUMBER") "R0805_10R_1%_0.125W_200PPM")
        (field (name "POWER") "0.125W")
        (field (name "AUTHOR") "CERN DEM JLC")
      )
      (libsource (lib "Resistors") (part "Resistor - 1%"))
    )
    (comp (ref "R89")
      (value "1k8")
      (footprint "RESC1608X55N")
      (description "Resistor - 1%")
      (fields
        (field (name "PART NUMBER") "R0603_1K8_1%_0.1W_100PPM")
        (field (name "POWER") "0.1W")
        (field (name "AUTHOR") "CERN DEM JLC")
      )
      (libsource (lib "") (part "Resistor - 1%_1"))
    )
    (comp (ref "R90")
      (value "10k")
      (footprint "RESC1005X40N")
      (description "Resistor - 1%")
      (fields
        (field (name "PART NUMBER") "R0402_10K_1%_0.0625W_100PPM")
        (field (name "POWER") "0.0625W")
        (field (name "AUTHOR") "CERN DEM JLC")
      )
      (libsource (lib "Resistors") (part "Resistor - 1%"))
    )
    (comp (ref "R94")
      (value "1k3")
      (footprint "RESC1608X55N")
      (description "Resistor - 1%")
      (fields
        (field (name "PART NUMBER") "R0603_1K3_1%_0.1W_100PPM")
        (field (name "POWER") "0.1W")
        (field (name "AUTHOR") "CERN DEM JLC")
      )
      (libsource (lib "Resistors") (part "Resistor - 1%"))
    )
    (comp (ref "R95")
      (value "1k5")
      (footprint "RESC1005X40N")
      (description "Resistor - 1%")
      (fields
        (field (name "PART NUMBER") "R0402_1K5_1%_0.0625W_100PPM")
        (field (name "POWER") "0.0625W")
        (field (name "AUTHOR") "CERN DEM JLC")
      )
      (libsource (lib "Resistors") (part "Resistor - 1%"))
    )
    (comp (ref "R96")
      (value "82k")
      (footprint "RESC1608X55N")
      (description "Resistor - 1%")
      (fields
        (field (name "PART NUMBER") "R0603_82K_1%_0.1W_100PPM")
        (field (name "POWER") "0.1W")
        (field (name "AUTHOR") "CERN DEM JLC")
      )
      (libsource (lib "Resistors") (part "Resistor - 1%"))
    )
    (comp (ref "R97")
      (value "33")
      (footprint "RESC1005X40N")
      (description "Resistor - 1%")
      (fields
        (field (name "PART NUMBER") "R0402_33R_1%_0.0625W_100PPM")
        (field (name "POWER") "0.0625W")
        (field (name "AUTHOR") "CERN DEM JLC")
      )
      (libsource (lib "Resistors") (part "Resistor - 1%"))
    )
    (comp (ref "R100")
      (value "6k8")
      (footprint "RESC1005X40N")
      (description "Resistor - 1%")
      (fields
        (field (name "PART NUMBER") "R0402_6K8_1%_0.0625W_100PPM")
        (field (name "POWER") "0.0625W")
        (field (name "AUTHOR") "CERN DEM JLC")
      )
      (libsource (lib "Resistors") (part "Resistor - 1%"))
    )
    (comp (ref "R101")
      (value "10k")
      (footprint "RESC1005X40N")
      (description "Resistor - 1%")
      (fields
        (field (name "PART NUMBER") "R0402_10K_1%_0.0625W_100PPM")
        (field (name "POWER") "0.0625W")
        (field (name "AUTHOR") "CERN DEM JLC")
      )
      (libsource (lib "Resistors") (part "Resistor - 1%"))
    )
    (comp (ref "R102")
      (value "240k")
      (footprint "RESC1005X40N")
      (description "Resistor - 1%")
      (fields
        (field (name "PART NUMBER") "R0402_240K_1%_0.0625W_100PPM")
        (field (name "POWER") "0.0625W")
        (field (name "AUTHOR") "CERN DEM JLC")
      )
      (libsource (lib "Resistors") (part "Resistor - 1%"))
    )
    (comp (ref "R103")
      (value "51k")
      (footprint "RESC1005X40N")
      (description "Resistor - 1%")
      (fields
        (field (name "PART NUMBER") "R0402_51K_1%_0.0625W_100PPM")
        (field (name "POWER") "0.0625W")
        (field (name "AUTHOR") "CERN DEM JLC")
      )
      (libsource (lib "Resistors") (part "Resistor - 1%"))
    )
    (comp (ref "R104")
      (value "2k")
      (footprint "RESC1005X40N")
      (description "Resistor - 1%")
      (fields
        (field (name "PART NUMBER") "R0402_2K_1%_0.0625W_100PPM")
        (field (name "POWER") "0.0625W")
        (field (name "AUTHOR") "CERN DEM JLC")
      )
      (libsource (lib "Resistors") (part "Resistor - 1%"))
    )
    (comp (ref "R105")
      (value "10")
      (footprint "RESC2012X60N")
      (description "Resistor - 1%")
      (fields
        (field (name "PART NUMBER") "R0805_10R_1%_0.125W_200PPM")
        (field (name "POWER") "0.125W")
        (field (name "AUTHOR") "CERN DEM JLC")
      )
      (libsource (lib "Resistors") (part "Resistor - 1%"))
    )
    (comp (ref "R121")
      (value "10k")
      (footprint "RESC1005X40N")
      (description "Resistor - 1%")
      (fields
        (field (name "PART NUMBER") "R0402_10K_1%_0.0625W_100PPM")
        (field (name "POWER") "0.0625W")
        (field (name "AUTHOR") "CERN DEM JLC")
      )
      (libsource (lib "Resistors") (part "Resistor - 1%"))
    )
    (comp (ref "R124")
      (value "33")
      (footprint "RESC1005X40N")
      (description "Resistor - 1%")
      (fields
        (field (name "PART NUMBER") "R0402_33R_1%_0.0625W_100PPM")
        (field (name "POWER") "0.0625W")
        (field (name "AUTHOR") "CERN DEM JLC")
      )
      (libsource (lib "Resistors") (part "Resistor - 1%"))
    )
    (comp (ref "R128")
      (value "100k")
      (footprint "RESC1005X40N")
      (description "Resistor - 1%")
      (fields
        (field (name "TOLERANCE") "±1%")
        (field (name "PART NUMBER") "R0402_100K_1%_0.0625W_100PPM")
        (field (name "POWER") "0.0625W")
        (field (name "AUTHOR") "CERN DEM JLC")
      )
      (libsource (lib "Resistors") (part "Resistor - 1%"))
    )
    (comp (ref "R131")
      (value "100")
      (footprint "RESC1005X40N")
      (description "Resistor - 1%")
      (fields
        (field (name "PART NUMBER") "R0402_100R_1%_0.0625W_100PPM")
        (field (name "POWER") "0.0625W")
        (field (name "AUTHOR") "CERN DEM JLC")
      )
      (libsource (lib "Resistors") (part "Resistor - 1%"))
    )
    (comp (ref "R138")
      (value "100k")
      (footprint "RESC1005X40N")
      (description "Resistor - 1%")
      (fields
        (field (name "TOLERANCE") "±1%")
        (field (name "PART NUMBER") "R0402_100K_1%_0.0625W_100PPM")
        (field (name "POWER") "0.0625W")
        (field (name "AUTHOR") "CERN DEM JLC")
      )
      (libsource (lib "Resistors") (part "Resistor - 1%"))
    )
    (comp (ref "R139")
      (value "100")
      (footprint "RESC1005X40N")
      (description "Resistor - 1%")
      (fields
        (field (name "PART NUMBER") "R0402_100R_1%_0.0625W_100PPM")
        (field (name "POWER") "0.0625W")
        (field (name "AUTHOR") "CERN DEM JLC")
      )
      (libsource (lib "Resistors") (part "Resistor - 1%"))
    )
    (comp (ref "R141")
      (value "10k")
      (footprint "RESC1005X40N")
      (description "Resistor - 1%")
      (fields
        (field (name "PART NUMBER") "R0402_10K_1%_0.0625W_100PPM")
        (field (name "POWER") "0.0625W")
        (field (name "AUTHOR") "CERN DEM JLC")
      )
      (libsource (lib "Resistors") (part "Resistor - 1%"))
    )
    (comp (ref "R154")
      (value "10k")
      (footprint "RESC1005X40N")
      (description "Resistor - 1%")
      (fields
        (field (name "PART NUMBER") "R0402_10K_1%_0.0625W_100PPM")
        (field (name "POWER") "0.0625W")
        (field (name "AUTHOR") "CERN DEM JLC")
      )
      (libsource (lib "Resistors") (part "Resistor - 1%"))
    )
    (comp (ref "R219")
      (value "162k")
      (footprint "RESC1005X40N")
      (description "Resistor - 1%")
      (fields
        (field (name "TOLERANCE") "±1%")
        (field (name "PART NUMBER") "R0402_162K_1%_0.063W_100PPM")
        (field (name "POWER") "0.063W")
        (field (name "AUTHOR") "CERN DEM BC")
      )
      (libsource (lib "Resistors") (part "Resistor - 1%"))
    )
    (comp (ref "R221")
      (value "162k")
      (footprint "RESC1005X40N")
      (description "Resistor - 1%")
      (fields
        (field (name "TOLERANCE") "±1%")
        (field (name "PART NUMBER") "R0402_162K_1%_0.063W_100PPM")
        (field (name "POWER") "0.063W")
        (field (name "AUTHOR") "CERN DEM BC")
      )
      (libsource (lib "Resistors") (part "Resistor - 1%"))
    )
    (comp (ref "R222")
      (value "2k74")
      (footprint "RESC1608X55N")
      (description "Resistor - 0.1%")
      (fields
        (field (name "TOLERANCE") "±0.1%")
        (field (name "PART NUMBER") "R0603_2K74_0.1%_0.063W_10PPM")
        (field (name "POWER") "0.063W")
        (field (name "AUTHOR") "CERN DEM JLC")
      )
      (libsource (lib "Resistors") (part "Resistor - 0.1%"))
    )
    (comp (ref "R227")
      (value "0")
      (footprint "RESC1005X40N")
      (description "Resistor")
      (fields
        (field (name "PART NUMBER") "R0402_0R_JUMPER")
        (field (name "MANUFACTURER") "GENERIC")
        (field (name "AUTHOR") "CERN DEM JLC")
      )
      (libsource (lib "Resistors") (part "Resistor"))
    )
    (comp (ref "R228")
      (value "0")
      (footprint "RESC1005X40N")
      (description "Resistor")
      (fields
        (field (name "PART NUMBER") "R0402_0R_JUMPER")
        (field (name "MANUFACTURER") "GENERIC")
        (field (name "AUTHOR") "CERN DEM JLC")
      )
      (libsource (lib "Resistors") (part "Resistor"))
    )
    (comp (ref "R229")
      (value "0")
      (footprint "RESC1005X40N")
      (description "Resistor")
      (fields
        (field (name "PART NUMBER") "R0402_0R_JUMPER")
        (field (name "MANUFACTURER") "GENERIC")
        (field (name "AUTHOR") "CERN DEM JLC")
      )
      (libsource (lib "Resistors") (part "Resistor"))
    )
    (comp (ref "R230")
      (value "0")
      (footprint "RESC1005X40N")
      (description "Resistor")
      (fields
        (field (name "PART NUMBER") "R0402_0R_JUMPER")
        (field (name "MANUFACTURER") "GENERIC")
        (field (name "AUTHOR") "CERN DEM JLC")
      )
      (libsource (lib "Resistors") (part "Resistor"))
    )
    (comp (ref "R231")
      (value "162k")
      (footprint "RESC1005X40N")
      (description "Resistor - 1%")
      (fields
        (field (name "TOLERANCE") "±1%")
        (field (name "PART NUMBER") "R0402_162K_1%_0.063W_100PPM")
        (field (name "POWER") "0.063W")
        (field (name "AUTHOR") "CERN DEM BC")
      )
      (libsource (lib "Resistors") (part "Resistor - 1%"))
    )
    (comp (ref "T3")
      (value "SI4425DDY-T1-GE3")
      (footprint "SOIC127P600X175-8N")
      (description "-30V -19.7A P-Channel MOSFET")
      (fields (field (name "MANUFACTURER") "VISHAY SILICONIX") (field (name "AUTHOR") "CERN DEM MR"))
      (libsource (lib "ICs And Semiconductors") (part "SI4425DDY"))
    )
    (comp (ref "T4")
      (value "FDN86246")
      (footprint "SOT95P237X112-3N")
      (description "N-CHANNEL MOSFET WITH DIODE")
      (fields (field (name "MANUFACTURER") "ON SEMICONDUCTOR") (field (name "AUTHOR") "CERN DEM BC"))
      (libsource (lib "ICs And Semiconductors") (part "N-MOSFET-D 1G 2S 3D"))
    )
    (comp (ref "T5")
      (value "BC857BV")
      (footprint "SOTFL50P160X60-6N")
      (description "45V, 100mA PNP General Purpose Double Transistor")
      (fields (field (name "MANUFACTURER") "NXP SEMICONDUCTORS") (field (name "AUTHOR") "CERN DEM JLC"))
      (libsource (lib "ICs And Semiconductors") (part "BC857BV"))
    )
    (comp (ref "T6")
      (value "BSS138LT1G")
      (footprint "SOT95P240X110-3N")
      (description "N-CHANNEL MOSFET WITH DIODE")
      (fields (field (name "MANUFACTURER") "ON SEMICONDUCTOR") (field (name "AUTHOR") "CERN DEM JLC"))
      (libsource (lib "") (part "N-MOSFET-D 1G 2S 3D_1"))
    )
    (comp (ref "T7")
      (value "BSS84AK")
      (footprint "SOT95P230X110-3N")
      (description "50V, 180mA P-Channel Trench MOSFET")
      (fields (field (name "MANUFACTURER") "NXP SEMICONDUCTORS") (field (name "AUTHOR") "CERN DEM JLC"))
      (libsource (lib "ICs And Semiconductors") (part "BSS84"))
    )
    (comp (ref "T8")
      (value "BSS138LT1G")
      (footprint "SOT95P240X110-3N")
      (description "N-CHANNEL MOSFET WITH DIODE")
      (fields (field (name "MANUFACTURER") "ON SEMICONDUCTOR") (field (name "AUTHOR") "CERN DEM JLC"))
      (libsource (lib "ICs And Semiconductors") (part "N-MOSFET-D 1G 2S 3D"))
    )
    (comp (ref "TP6")
      (value "Test Point")
      (footprint "TPS127")
      (fields (field (name "PART NUMBER") "SMD_PAD_1.27X1.27MM") (field (name "AUTHOR") "CERN DEM JLC"))
      (libsource (lib "Eletro-mechanical") (part "Test Point"))
    )
    (comp (ref "TP7")
      (value "Test Point")
      (footprint "TPS127")
      (fields (field (name "PART NUMBER") "SMD_PAD_1.27X1.27MM") (field (name "AUTHOR") "CERN DEM JLC"))
      (libsource (lib "Eletro-mechanical") (part "Test Point"))
    )
    (comp (ref "TP8")
      (value "Test Point")
      (footprint "TPS127")
      (fields (field (name "PART NUMBER") "SMD_PAD_1.27X1.27MM") (field (name "AUTHOR") "CERN DEM JLC"))
      (libsource (lib "Eletro-mechanical") (part "Test Point"))
    )
    (comp (ref "TP9")
      (value "Test Point")
      (footprint "TPS127")
      (fields (field (name "PART NUMBER") "SMD_PAD_1.27X1.27MM") (field (name "AUTHOR") "CERN DEM JLC"))
      (libsource (lib "Eletro-mechanical") (part "Test Point"))
    )
    (comp (ref "TP10")
      (value "Test Point")
      (footprint "TPS127")
      (fields (field (name "PART NUMBER") "SMD_PAD_1.27X1.27MM") (field (name "AUTHOR") "CERN DEM JLC"))
      (libsource (lib "Eletro-mechanical") (part "Test Point"))
    )
    (comp (ref "TP11")
      (value "Test Point")
      (footprint "TPS127")
      (fields (field (name "PART NUMBER") "SMD_PAD_1.27X1.27MM") (field (name "AUTHOR") "CERN DEM JLC"))
      (libsource (lib "Eletro-mechanical") (part "Test Point"))
    )
  )
  (nets
    (net (code "1") (name "/AT_EVENT") (class "Default")
      (node (ref "IC6") (pin "4") (pinfunction "C_4") (pintype "open_collector"))
      (node (ref "R67") (pin "1") (pinfunction "1_1") (pintype "passive"))
    )
    (net (code "2") (name "/CPU_RESETn") (class "Default")
      (node (ref "T6") (pin "1") (pinfunction "G_1") (pintype "passive"))
    )
    (net (code "3") (name "/FAN_PWM") (class "Default")
      (node (ref "C82") (pin "1") (pinfunction "1_1") (pintype "passive"))
    )
    (net (code "4") (name "/I_meas_P12V0") (class "Default")
      (node (ref "C89") (pin "1") (pinfunction "1_1") (pintype "passive"))
      (node (ref "R141") (pin "2") (pinfunction "2_2") (pintype "passive"))
    )
    (net (code "5") (name "/P12V0_POE") (class "Default")
      (node (ref "C3") (pin "1") (pinfunction "1_1") (pintype "passive"))
      (node (ref "C4") (pin "1") (pinfunction "1_1") (pintype "passive"))
      (node (ref "IC3") (pin "8") (pinfunction "+VDC_8") (pintype "input"))
      (node (ref "R30") (pin "2") (pinfunction "2_2") (pintype "passive"))
      (node (ref "T3") (pin "5") (pinfunction "D_5") (pintype "passive"))
      (node (ref "T3") (pin "6") (pinfunction "D_6") (pintype "passive"))
      (node (ref "T3") (pin "7") (pinfunction "D_7") (pintype "passive"))
      (node (ref "T3") (pin "8") (pinfunction "D_8") (pintype "passive"))
      (node (ref "T5") (pin "4") (pinfunction "E_4") (pintype "passive"))
    )
    (net (code "6") (name "/POE_PWR_SRC") (class "Default")
      (node (ref "R30") (pin "1") (pinfunction "1_1") (pintype "passive"))
      (node (ref "R31") (pin "2") (pinfunction "2_2") (pintype "passive"))
    )
    (net (code "7") (name "/POE_VC+") (class "Default")
      (node (ref "L1") (pin "1") (pinfunction "1_1") (pintype "passive"))
      (node (ref "R14") (pin "2") (pinfunction "2_2") (pintype "passive"))
    )
    (net (code "8") (name "/POE_VC-") (class "Default")
      (node (ref "R35") (pin "1") (pinfunction "1_1") (pintype "passive"))
      (node (ref "R64") (pin "1") (pinfunction "1_1") (pintype "passive"))
      (node (ref "R66") (pin "1") (pinfunction "1_1") (pintype "passive"))
      (node (ref "T4") (pin "2") (pinfunction "S_2") (pintype "passive"))
    )
    (net (code "9") (name "/TACHO") (class "Default")
      (node (ref "R9") (pin "1") (pinfunction "1_1") (pintype "passive"))
    )
    (net (code "10") (name "/clkoutA") (class "Default")
      (node (ref "B20") (pin "1") (pinfunction "1_1") (pintype "bidirectional"))
      (node (ref "IC34") (pin "B5") (pinfunction "CLKOUT_B5") (pintype "output"))
      (node (ref "IC35") (pin "A5") (pinfunction "CLKIN_A5") (pintype "input"))
    )
    (net (code "11") (name "/clkoutB") (class "Default")
      (node (ref "B21") (pin "1") (pinfunction "1_1") (pintype "bidirectional"))
      (node (ref "IC35") (pin "B5") (pinfunction "CLKOUT_B5") (pintype "output"))
      (node (ref "IC37") (pin "A5") (pinfunction "CLKIN_A5") (pintype "input"))
    )
    (net (code "12") (name "GND") (class "Default")
      (node (ref "C10") (pin "1") (pinfunction "1_1") (pintype "passive"))
      (node (ref "C101") (pin "1") (pinfunction "1_1") (pintype "passive"))
      (node (ref "C11") (pin "1") (pinfunction "1_1") (pintype "passive"))
      (node (ref "C112") (pin "2") (pinfunction "2_2") (pintype "passive"))
      (node (ref "C113") (pin "1") (pinfunction "1_1") (pintype "passive"))
      (node (ref "C114") (pin "2") (pinfunction "2_2") (pintype "passive"))
      (node (ref "C115") (pin "1") (pinfunction "1_1") (pintype "passive"))
      (node (ref "C117") (pin "1") (pinfunction "1_1") (pintype "passive"))
      (node (ref "C12") (pin "1") (pinfunction "1_1") (pintype "passive"))
      (node (ref "C13") (pin "1") (pinfunction "1_1") (pintype "passive"))
      (node (ref "C14") (pin "1") (pinfunction "1_1") (pintype "passive"))
      (node (ref "C15") (pin "2") (pinfunction "2_2") (pintype "passive"))
      (node (ref "C152") (pin "1") (pinfunction "1_1") (pintype "passive"))
      (node (ref "C155") (pin "1") (pinfunction "1_1") (pintype "passive"))
      (node (ref "C156") (pin "1") (pinfunction "1_1") (pintype "passive"))
      (node (ref "C157") (pin "1") (pinfunction "1_1") (pintype "passive"))
      (node (ref "C158") (pin "1") (pinfunction "1_1") (pintype "passive"))
      (node (ref "C159") (pin "2") (pinfunction "2_2") (pintype "passive"))
      (node (ref "C163") (pin "1") (pinfunction "1_1") (pintype "passive"))
      (node (ref "C164") (pin "1") (pinfunction "1_1") (pintype "passive"))
      (node (ref "C165") (pin "2") (pinfunction "2_2") (pintype "passive"))
      (node (ref "C166") (pin "1") (pinfunction "1_1") (pintype "passive"))
      (node (ref "C167") (pin "1") (pinfunction "1_1") (pintype "passive"))
      (node (ref "C19") (pin "2") (pinfunction "2_2") (pintype "passive"))
      (node (ref "C3") (pin "2") (pinfunction "2_2") (pintype "passive"))
      (node (ref "C34") (pin "1") (pinfunction "1_1") (pintype "passive"))
      (node (ref "C37") (pin "2") (pinfunction "2_2") (pintype "passive"))
      (node (ref "C38") (pin "2") (pinfunction "2_2") (pintype "passive"))
      (node (ref "C4") (pin "2") (pinfunction "2_2") (pintype "passive"))
      (node (ref "C6") (pin "1") (pinfunction "1_1") (pintype "passive"))
      (node (ref "C7") (pin "1") (pinfunction "1_1") (pintype "passive"))
      (node (ref "C78") (pin "1") (pinfunction "1_1") (pintype "passive"))
      (node (ref "C8") (pin "1") (pinfunction "1_1") (pintype "passive"))
      (node (ref "C89") (pin "2") (pinfunction "2_2") (pintype "passive"))
      (node (ref "C9") (pin "1") (pinfunction "1_1") (pintype "passive"))
      (node (ref "C91") (pin "2") (pinfunction "2_2") (pintype "passive"))
      (node (ref "D12") (pin "2") (pinfunction "A_2") (pintype "passive"))
      (node (ref "D24") (pin "2") (pinfunction "A_2") (pintype "passive"))
      (node (ref "D25") (pin "2") (pinfunction "A_2") (pintype "passive"))
      (node (ref "IC12") (pin "2") (pinfunction "GND_2") (pintype "power_in"))
      (node (ref "IC15") (pin "1") (pinfunction "GND_1") (pintype "power_in"))
      (node (ref "IC15") (pin "5") (pinfunction "PGND_5") (pintype "power_in"))
      (node (ref "IC15") (pin "56") (pinfunction "GND_56") (pintype "power_in"))
      (node (ref "IC15") (pin "64") (pinfunction "GND_64") (pintype "power_in"))
      (node (ref "IC15") (pin "65") (pinfunction "EPAD_65") (pintype "power_in"))
      (node (ref "IC16") (pin "4") (pinfunction "GND_4") (pintype "power_in"))
      (node (ref "IC17") (pin "2") (pinfunction "GND_2") (pintype "power_in"))
      (node (ref "IC18") (pin "3") (pinfunction "GND_3") (pintype "power_in"))
      (node (ref "IC18") (pin "6") (pinfunction "GND_6") (pintype "power_in"))
      (node (ref "IC18") (pin "9") (pinfunction "EP_9") (pintype "power_in"))
      (node (ref "IC22") (pin "2") (pinfunction "GND_2") (pintype "power_in"))
      (node (ref "IC3") (pin "10") (pinfunction "-VDC_10") (pintype "power_in"))
      (node (ref "IC3") (pin "7") (pinfunction "-VDC_7") (pintype "power_in"))
      (node (ref "IC34") (pin "B3") (pinfunction "GND_B3") (pintype "power_in"))
      (node (ref "IC34") (pin "B4") (pinfunction "SGND_B4") (pintype "power_in"))
      (node (ref "IC34") (pin "C3") (pinfunction "GND_C3") (pintype "power_in"))
      (node (ref "IC34") (pin "D3") (pinfunction "GND_D3") (pintype "power_in"))
      (node (ref "IC34") (pin "D4") (pinfunction "GND_D4") (pintype "power_in"))
      (node (ref "IC34") (pin "E3") (pinfunction "GND_E3") (pintype "power_in"))
      (node (ref "IC35") (pin "B3") (pinfunction "GND_B3") (pintype "power_in"))
      (node (ref "IC35") (pin "B4") (pinfunction "SGND_B4") (pintype "power_in"))
      (node (ref "IC35") (pin "C3") (pinfunction "GND_C3") (pintype "power_in"))
      (node (ref "IC35") (pin "D3") (pinfunction "GND_D3") (pintype "power_in"))
      (node (ref "IC35") (pin "D4") (pinfunction "GND_D4") (pintype "power_in"))
      (node (ref "IC35") (pin "E3") (pinfunction "GND_E3") (pintype "power_in"))
      (node (ref "IC37") (pin "B3") (pinfunction "GND_B3") (pintype "power_in"))
      (node (ref "IC37") (pin "B4") (pinfunction "SGND_B4") (pintype "power_in"))
      (node (ref "IC37") (pin "C3") (pinfunction "GND_C3") (pintype "power_in"))
      (node (ref "IC37") (pin "D3") (pinfunction "GND_D3") (pintype "power_in"))
      (node (ref "IC37") (pin "D4") (pinfunction "GND_D4") (pintype "power_in"))
      (node (ref "IC37") (pin "E3") (pinfunction "GND_E3") (pintype "power_in"))
      (node (ref "IC6") (pin "3") (pinfunction "E_3") (pintype "open_emitter"))
      (node (ref "J4") (pin "1") (pinfunction "1_1") (pintype "bidirectional"))
      (node (ref "J5") (pin "1") (pinfunction "1_1") (pintype "bidirectional"))
      (node (ref "J5") (pin "2") (pinfunction "2_2") (pintype "bidirectional"))
      (node (ref "J6") (pin "1") (pinfunction "1_1") (pintype "bidirectional"))
      (node (ref "LD10") (pin "1") (pinfunction "C_1") (pintype "passive"))
      (node (ref "LD2") (pin "1") (pinfunction "C_1") (pintype "passive"))
      (node (ref "LD3") (pin "1") (pinfunction "C_1") (pintype "passive"))
      (node (ref "LD4") (pin "1") (pinfunction "C_1") (pintype "passive"))
      (node (ref "LD6") (pin "1") (pinfunction "C_1") (pintype "passive"))
      (node (ref "LD9") (pin "1") (pinfunction "C_1") (pintype "passive"))
      (node (ref "R104") (pin "1") (pinfunction "1_1") (pintype "passive"))
      (node (ref "R139") (pin "1") (pinfunction "1_1") (pintype "passive"))
      (node (ref "R154") (pin "1") (pinfunction "1_1") (pintype "passive"))
      (node (ref "R219") (pin "1") (pinfunction "1_1") (pintype "passive"))
      (node (ref "R221") (pin "1") (pinfunction "1_1") (pintype "passive"))
      (node (ref "R222") (pin "1") (pinfunction "1_1") (pintype "passive"))
      (node (ref "R228") (pin "1") (pinfunction "1_1") (pintype "passive"))
      (node (ref "R230") (pin "1") (pinfunction "1_1") (pintype "passive"))
      (node (ref "R231") (pin "1") (pinfunction "1_1") (pintype "passive"))
      (node (ref "R31") (pin "1") (pinfunction "1_1") (pintype "passive"))
      (node (ref "R68") (pin "1") (pinfunction "1_1") (pintype "passive"))
      (node (ref "R85") (pin "1") (pinfunction "1_1") (pintype "passive"))
      (node (ref "T6") (pin "2") (pinfunction "S_2") (pintype "passive"))
      (node (ref "T8") (pin "2") (pinfunction "S_2") (pintype "passive"))
      (node (ref "TP9") (pin "1") (pinfunction "1_1") (pintype "bidirectional"))
    )
    (net (code "13") (name "Net-(C5-Pad2)") (class "Default")
      (node (ref "C5") (pin "2") (pinfunction "2_2") (pintype "passive"))
      (node (ref "L1") (pin "2") (pinfunction "2_2") (pintype "passive"))
      (node (ref "L6") (pin "1") (pinfunction "1_1") (pintype "passive"))
    )
    (net (code "14") (name "Net-(C27-Pad1)") (class "Default")
      (node (ref "C27") (pin "1") (pinfunction "1_1") (pintype "passive"))
      (node (ref "R96") (pin "2") (pinfunction "2_2") (pintype "passive"))
    )
    (net (code "15") (name "Net-(C152-Pad2)") (class "Default")
      (node (ref "C152") (pin "2") (pinfunction "2_2") (pintype "passive"))
      (node (ref "IC15") (pin "2") (pinfunction "PVDD_2") (pintype "power_in"))
      (node (ref "IC15") (pin "3") (pinfunction "PVDD_3") (pintype "power_in"))
      (node (ref "IC15") (pin "49") (pinfunction "ANODE_49") (pintype "passive"))
      (node (ref "IC15") (pin "50") (pinfunction "ANODE_50") (pintype "passive"))
      (node (ref "IC15") (pin "62") (pinfunction "5VDD_62") (pintype "power_in"))
      (node (ref "IC15") (pin "63") (pinfunction "5VDD_63") (pintype "power_in"))
    )
    (net (code "16") (name "Net-(D12-C)") (class "Default")
      (node (ref "D12") (pin "1") (pinfunction "C_1") (pintype "passive"))
      (node (ref "J6") (pin "2") (pinfunction "2_2") (pintype "bidirectional"))
      (node (ref "T7") (pin "3") (pinfunction "D_3") (pintype "passive"))
    )
    (net (code "17") (name "Net-(D28-A)") (class "Default")
      (node (ref "C82") (pin "2") (pinfunction "2_2") (pintype "passive"))
      (node (ref "D28") (pin "2") (pinfunction "A_2") (pintype "passive"))
      (node (ref "R121") (pin "1") (pinfunction "1_1") (pintype "passive"))
      (node (ref "T8") (pin "1") (pinfunction "G_1") (pintype "passive"))
    )
    (net (code "18") (name "Net-(IC3-AT-DET)") (class "Default")
      (node (ref "IC3") (pin "3") (pinfunction "AT-DET_3") (pintype "input"))
      (node (ref "IC6") (pin "2") (pinfunction "C_2") (pintype "input"))
    )
    (net (code "19") (name "Net-(IC3-VIN+)") (class "Default")
      (node (ref "C6") (pin "2") (pinfunction "2_2") (pintype "passive"))
      (node (ref "IC3") (pin "1") (pinfunction "VIN+_1") (pintype "input"))
      (node (ref "IC6") (pin "1") (pinfunction "A_1") (pintype "input"))
      (node (ref "L6") (pin "4") (pinfunction "4_4") (pintype "passive"))
    )
    (net (code "20") (name "Net-(IC3-VIN-)") (class "Default")
      (node (ref "C7") (pin "2") (pinfunction "2_2") (pintype "passive"))
      (node (ref "IC3") (pin "2") (pinfunction "VIN-_2") (pintype "output"))
      (node (ref "L6") (pin "3") (pinfunction "3_3") (pintype "passive"))
    )
    (net (code "21") (name "Net-(IC4-A)") (class "Default")
      (node (ref "IC4") (pin "1") (pinfunction "A_1") (pintype "input"))
      (node (ref "R16") (pin "1") (pinfunction "1_1") (pintype "passive"))
    )
    (net (code "22") (name "Net-(IC4-C-Pad4)") (class "Default")
      (node (ref "IC4") (pin "4") (pinfunction "C_4") (pintype "open_collector"))
      (node (ref "R14") (pin "1") (pinfunction "1_1") (pintype "passive"))
      (node (ref "R35") (pin "2") (pinfunction "2_2") (pintype "passive"))
    )
    (net (code "23") (name "Net-(IC4-E)") (class "Default")
      (node (ref "IC4") (pin "3") (pinfunction "E_3") (pintype "open_emitter"))
      (node (ref "R66") (pin "2") (pinfunction "2_2") (pintype "passive"))
      (node (ref "T4") (pin "1") (pinfunction "G_1") (pintype "passive"))
    )
    (net (code "24") (name "Net-(IC12-VIN)") (class "Default")
      (node (ref "C114") (pin "1") (pinfunction "1_1") (pintype "passive"))
      (node (ref "IC12") (pin "1") (pinfunction "VIN_1") (pintype "input"))
      (node (ref "R124") (pin "2") (pinfunction "2_2") (pintype "passive"))
    )
    (net (code "25") (name "Net-(IC15-EN)") (class "Default")
      (node (ref "IC15") (pin "59") (pinfunction "EN_59") (pintype "passive"))
      (node (ref "R138") (pin "2") (pinfunction "2_2") (pintype "passive"))
    )
    (net (code "26") (name "Net-(IC15-FB)") (class "Default")
      (node (ref "C118") (pin "1") (pinfunction "1_1") (pintype "passive"))
      (node (ref "IC15") (pin "48") (pinfunction "RIB_48") (pintype "passive"))
      (node (ref "IC15") (pin "57") (pinfunction "FB_57") (pintype "input"))
      (node (ref "R86") (pin "1") (pinfunction "1_1") (pintype "passive"))
      (node (ref "R89") (pin "2") (pinfunction "2_2") (pintype "passive"))
    )
    (net (code "27") (name "Net-(IC15-FREQ)") (class "Default")
      (node (ref "IC15") (pin "61") (pinfunction "FREQ_61") (pintype "passive"))
      (node (ref "R128") (pin "2") (pinfunction "2_2") (pintype "passive"))
    )
    (net (code "28") (name "Net-(IC15-ILIM)") (class "Default")
      (node (ref "C34") (pin "2") (pinfunction "2_2") (pintype "passive"))
      (node (ref "IC15") (pin "4") (pinfunction "ILIM_4") (pintype "passive"))
      (node (ref "R95") (pin "1") (pinfunction "1_1") (pintype "passive"))
    )
    (net (code "29") (name "Net-(IC15-SW-Pad10)") (class "Default")
      (node (ref "IC15") (pin "10") (pinfunction "SW_10") (pintype "passive"))
      (node (ref "IC15") (pin "38") (pinfunction "SW_38") (pintype "passive"))
      (node (ref "IC15") (pin "39") (pinfunction "SW_39") (pintype "passive"))
      (node (ref "IC15") (pin "40") (pinfunction "SW_40") (pintype "passive"))
      (node (ref "IC15") (pin "41") (pinfunction "SW_41") (pintype "passive"))
      (node (ref "IC15") (pin "42") (pinfunction "SW_42") (pintype "passive"))
      (node (ref "IC15") (pin "43") (pinfunction "SW_43") (pintype "passive"))
      (node (ref "IC15") (pin "44") (pinfunction "SW_44") (pintype "passive"))
      (node (ref "IC15") (pin "7") (pinfunction "SW_7") (pintype "passive"))
      (node (ref "IC15") (pin "8") (pinfunction "SW_8") (pintype "passive"))
      (node (ref "IC15") (pin "9") (pinfunction "SW_9") (pintype "passive"))
      (node (ref "R95") (pin "2") (pinfunction "2_2") (pintype "passive"))
    )
    (net (code "30") (name "Net-(IC16-COMP)") (class "Default")
      (node (ref "IC16") (pin "7") (pinfunction "COMP_7") (pintype "input"))
      (node (ref "R96") (pin "1") (pinfunction "1_1") (pintype "passive"))
    )
    (net (code "31") (name "Net-(IC16-IN)") (class "Default")
      (node (ref "C19") (pin "1") (pinfunction "1_1") (pintype "passive"))
      (node (ref "C37") (pin "1") (pinfunction "1_1") (pintype "passive"))
      (node (ref "IC16") (pin "2") (pinfunction "IN_2") (pintype "input"))
      (node (ref "R97") (pin "2") (pinfunction "2_2") (pintype "passive"))
    )
    (net (code "32") (name "Net-(IC17-FB)") (class "Default")
      (node (ref "IC17") (pin "5") (pinfunction "FB_5") (pintype "input"))
      (node (ref "R102") (pin "1") (pinfunction "1_1") (pintype "passive"))
      (node (ref "R103") (pin "2") (pinfunction "2_2") (pintype "passive"))
    )
    (net (code "33") (name "Net-(IC17-SW)") (class "Default")
      (node (ref "IC17") (pin "3") (pinfunction "SW_3") (pintype "power_in"))
      (node (ref "L8") (pin "1") (pinfunction "1_1") (pintype "passive"))
    )
    (net (code "34") (name "Net-(IC18-VIN)") (class "Default")
      (node (ref "C112") (pin "1") (pinfunction "1_1") (pintype "passive"))
      (node (ref "IC18") (pin "8") (pinfunction "VIN_8") (pintype "input"))
      (node (ref "R105") (pin "2") (pinfunction "2_2") (pintype "passive"))
    )
    (net (code "35") (name "Net-(IC22-OUT)") (class "Default")
      (node (ref "IC22") (pin "1") (pinfunction "OUT_1") (pintype "output"))
      (node (ref "R141") (pin "1") (pinfunction "1_1") (pintype "passive"))
      (node (ref "R154") (pin "2") (pinfunction "2_2") (pintype "passive"))
    )
    (net (code "36") (name "Net-(IC22-VIN-)") (class "Default")
      (node (ref "IC22") (pin "3") (pinfunction "VIN-_3") (pintype "input"))
      (node (ref "R131") (pin "1") (pinfunction "1_1") (pintype "passive"))
    )
    (net (code "37") (name "Net-(IC34-COMP)") (class "Default")
      (node (ref "IC34") (pin "A1") (pinfunction "COMP_A1") (pintype "input"))
      (node (ref "IC35") (pin "A1") (pinfunction "COMP_A1") (pintype "input"))
      (node (ref "IC37") (pin "A1") (pinfunction "COMP_A1") (pintype "input"))
    )
    (net (code "38") (name "Net-(IC34-FB)") (class "Default")
      (node (ref "IC34") (pin "B1") (pinfunction "FB_B1") (pintype "input"))
      (node (ref "IC35") (pin "B1") (pinfunction "FB_B1") (pintype "input"))
      (node (ref "IC37") (pin "B1") (pinfunction "FB_B1") (pintype "input"))
      (node (ref "R222") (pin "2") (pinfunction "2_2") (pintype "passive"))
    )
    (net (code "39") (name "Net-(IC34-FREQ)") (class "Default")
      (node (ref "IC34") (pin "A4") (pinfunction "FREQ_A4") (pintype "input"))
      (node (ref "R219") (pin "2") (pinfunction "2_2") (pintype "passive"))
    )
    (net (code "40") (name "Net-(IC34-INTVCC)") (class "Default")
      (node (ref "IC34") (pin "C4") (pinfunction "MODE_C4") (pintype "input"))
      (node (ref "IC34") (pin "E4") (pinfunction "INTVCC_E4") (pintype "power_in"))
      (node (ref "R227") (pin "2") (pinfunction "2_2") (pintype "passive"))
    )
    (net (code "41") (name "Net-(IC34-PGOOD)") (class "Default")
      (node (ref "B10") (pin "1") (pinfunction "1_1") (pintype "bidirectional"))
      (node (ref "IC34") (pin "C2") (pinfunction "PGOOD_C2") (pintype "open_collector"))
    )
    (net (code "42") (name "Net-(IC34-PHMODE)") (class "Default")
      (node (ref "IC34") (pin "B2") (pinfunction "PHMODE_B2") (pintype "input"))
      (node (ref "R227") (pin "1") (pinfunction "1_1") (pintype "passive"))
      (node (ref "R228") (pin "2") (pinfunction "2_2") (pintype "passive"))
    )
    (net (code "43") (name "Net-(IC34-TRACK{slash}SS)") (class "Default")
      (node (ref "C159") (pin "1") (pinfunction "1_1") (pintype "passive"))
      (node (ref "IC34") (pin "A2") (pinfunction "TRACK/SS_A2") (pintype "input"))
      (node (ref "IC35") (pin "A2") (pinfunction "TRACK/SS_A2") (pintype "input"))
      (node (ref "IC37") (pin "A2") (pinfunction "TRACK/SS_A2") (pintype "input"))
    )
    (net (code "44") (name "Net-(IC35-FREQ)") (class "Default")
      (node (ref "IC35") (pin "A4") (pinfunction "FREQ_A4") (pintype "input"))
      (node (ref "R221") (pin "2") (pinfunction "2_2") (pintype "passive"))
    )
    (net (code "45") (name "Net-(IC35-INTVCC)") (class "Default")
      (node (ref "IC35") (pin "C4") (pinfunction "MODE_C4") (pintype "input"))
      (node (ref "IC35") (pin "E4") (pinfunction "INTVCC_E4") (pintype "power_in"))
      (node (ref "R229") (pin "2") (pinfunction "2_2") (pintype "passive"))
    )
    (net (code "46") (name "Net-(IC35-PGOOD)") (class "Default")
      (node (ref "B19") (pin "1") (pinfunction "1_1") (pintype "bidirectional"))
      (node (ref "IC35") (pin "C2") (pinfunction "PGOOD_C2") (pintype "open_collector"))
    )
    (net (code "47") (name "Net-(IC35-PHMODE)") (class "Default")
      (node (ref "IC35") (pin "B2") (pinfunction "PHMODE_B2") (pintype "input"))
      (node (ref "R229") (pin "1") (pinfunction "1_1") (pintype "passive"))
      (node (ref "R230") (pin "2") (pinfunction "2_2") (pintype "passive"))
    )
    (net (code "48") (name "Net-(IC37-FREQ)") (class "Default")
      (node (ref "IC37") (pin "A4") (pinfunction "FREQ_A4") (pintype "input"))
      (node (ref "R231") (pin "2") (pinfunction "2_2") (pintype "passive"))
    )
    (net (code "49") (name "Net-(IC37-INTVCC)") (class "Default")
      (node (ref "IC37") (pin "C4") (pinfunction "MODE_C4") (pintype "input"))
      (node (ref "IC37") (pin "E4") (pinfunction "INTVCC_E4") (pintype "power_in"))
    )
    (net (code "50") (name "Net-(IC37-PGOOD)") (class "Default")
      (node (ref "B18") (pin "1") (pinfunction "1_1") (pintype "bidirectional"))
      (node (ref "IC37") (pin "C2") (pinfunction "PGOOD_C2") (pintype "open_collector"))
    )
    (net (code "51") (name "Net-(J6-Pad3)") (class "Default")
      (node (ref "J6") (pin "3") (pinfunction "3_3") (pintype "bidirectional"))
      (node (ref "R101") (pin "2") (pinfunction "2_2") (pintype "passive"))
      (node (ref "R9") (pin "2") (pinfunction "2_2") (pintype "passive"))
    )
    (net (code "52") (name "Net-(LD2-A)") (class "Default")
      (node (ref "LD2") (pin "2") (pinfunction "A_2") (pintype "passive"))
      (node (ref "R90") (pin "1") (pinfunction "1_1") (pintype "passive"))
    )
    (net (code "53") (name "Net-(LD3-A)") (class "Default")
      (node (ref "LD3") (pin "2") (pinfunction "A_2") (pintype "passive"))
      (node (ref "R94") (pin "2") (pinfunction "2_2") (pintype "passive"))
    )
    (net (code "54") (name "Net-(LD4-A)") (class "Default")
      (node (ref "LD4") (pin "2") (pinfunction "A_2") (pintype "passive"))
      (node (ref "R100") (pin "2") (pinfunction "2_2") (pintype "passive"))
    )
    (net (code "55") (name "Net-(LD6-A)") (class "Default")
      (node (ref "LD6") (pin "2") (pinfunction "A_2") (pintype "passive"))
      (node (ref "R10") (pin "2") (pinfunction "2_2") (pintype "passive"))
    )
    (net (code "56") (name "Net-(LD9-A)") (class "Default")
      (node (ref "LD9") (pin "2") (pinfunction "A_2") (pintype "passive"))
      (node (ref "R39") (pin "2") (pinfunction "2_2") (pintype "passive"))
    )
    (net (code "57") (name "Net-(LD10-A)") (class "Default")
      (node (ref "LD10") (pin "2") (pinfunction "A_2") (pintype "passive"))
      (node (ref "R54") (pin "2") (pinfunction "2_2") (pintype "passive"))
    )
    (net (code "58") (name "Net-(R103-Pad1)") (class "Default")
      (node (ref "R103") (pin "1") (pinfunction "1_1") (pintype "passive"))
      (node (ref "R104") (pin "2") (pinfunction "2_2") (pintype "passive"))
    )
    (net (code "59") (name "Net-(R105-Pad1)") (class "Default")
      (node (ref "R105") (pin "1") (pinfunction "1_1") (pintype "passive"))
      (node (ref "R88") (pin "2") (pinfunction "2_2") (pintype "passive"))
    )
    (net (code "60") (name "Net-(R139-Pad2)") (class "Default")
      (node (ref "R139") (pin "2") (pinfunction "2_2") (pintype "passive"))
      (node (ref "R89") (pin "1") (pinfunction "1_1") (pintype "passive"))
    )
    (net (code "61") (name "Net-(T4-D)") (class "Default")
      (node (ref "C5") (pin "1") (pinfunction "1_1") (pintype "passive"))
      (node (ref "L6") (pin "2") (pinfunction "2_2") (pintype "passive"))
      (node (ref "R64") (pin "2") (pinfunction "2_2") (pintype "passive"))
      (node (ref "T4") (pin "3") (pinfunction "D_3") (pintype "passive"))
    )
    (net (code "62") (name "Net-(T5A-B)") (class "Default")
      (node (ref "R65") (pin "1") (pinfunction "1_1") (pintype "passive"))
      (node (ref "T5") (pin "2") (pinfunction "B_2") (pintype "passive"))
    )
    (net (code "63") (name "Net-(T5A-C)") (class "Default")
      (node (ref "R68") (pin "2") (pinfunction "2_2") (pintype "passive"))
      (node (ref "T3") (pin "4") (pinfunction "S_4") (pintype "passive"))
      (node (ref "T5") (pin "6") (pinfunction "C_6") (pintype "passive"))
    )
    (net (code "64") (name "Net-(T5B-B)") (class "Default")
      (node (ref "R65") (pin "2") (pinfunction "2_2") (pintype "passive"))
      (node (ref "R85") (pin "2") (pinfunction "2_2") (pintype "passive"))
      (node (ref "T5") (pin "3") (pinfunction "C_3") (pintype "passive"))
      (node (ref "T5") (pin "5") (pinfunction "B_5") (pintype "passive"))
    )
    (net (code "65") (name "Net-(T6-D)") (class "Default")
      (node (ref "IC4") (pin "2") (pinfunction "C_2") (pintype "input"))
      (node (ref "T6") (pin "3") (pinfunction "D_3") (pintype "passive"))
    )
    (net (code "66") (name "Net-(T7-G)") (class "Default")
      (node (ref "R13") (pin "1") (pinfunction "1_1") (pintype "passive"))
      (node (ref "T7") (pin "1") (pinfunction "G_1") (pintype "passive"))
      (node (ref "T8") (pin "3") (pinfunction "D_3") (pintype "passive"))
    )
    (net (code "67") (name "P3V0REF") (class "Default")
      (node (ref "C27") (pin "2") (pinfunction "2_2") (pintype "passive"))
      (node (ref "C38") (pin "1") (pinfunction "1_1") (pintype "passive"))
      (node (ref "IC16") (pin "6") (pinfunction "OUT_6") (pintype "power_in"))
      (node (ref "R54") (pin "1") (pinfunction "1_1") (pintype "passive"))
      (node (ref "TP10") (pin "1") (pinfunction "1_1") (pintype "bidirectional"))
    )
    (net (code "68") (name "P3V3") (class "Default")
      (node (ref "C91") (pin "1") (pinfunction "1_1") (pintype "passive"))
      (node (ref "D2") (pin "2") (pinfunction "A_2") (pintype "passive"))
      (node (ref "D28") (pin "1") (pinfunction "C_1") (pintype "passive"))
      (node (ref "IC12") (pin "3") (pinfunction "EN_3") (pintype "input"))
      (node (ref "IC18") (pin "5") (pinfunction "EN/UVLO_5") (pintype "input"))
      (node (ref "L8") (pin "2") (pinfunction "2_2") (pintype "passive"))
      (node (ref "R101") (pin "1") (pinfunction "1_1") (pintype "passive"))
      (node (ref "R102") (pin "2") (pinfunction "2_2") (pintype "passive"))
      (node (ref "R121") (pin "2") (pinfunction "2_2") (pintype "passive"))
      (node (ref "R16") (pin "2") (pinfunction "2_2") (pintype "passive"))
      (node (ref "R67") (pin "2") (pinfunction "2_2") (pintype "passive"))
      (node (ref "R94") (pin "1") (pinfunction "1_1") (pintype "passive"))
      (node (ref "TP8") (pin "1") (pinfunction "1_1") (pintype "bidirectional"))
    )
    (net (code "69") (name "P3V3IO") (class "Default")
      (node (ref "C115") (pin "2") (pinfunction "2_2") (pintype "passive"))
      (node (ref "IC12") (pin "5") (pinfunction "VOUT_5") (pintype "power_in"))
    )
    (net (code "70") (name "P3V3_MP") (class "Default")
      (node (ref "D2") (pin "1") (pinfunction "C_1") (pintype "passive"))
      (node (ref "R10") (pin "1") (pinfunction "1_1") (pintype "passive"))
    )
    (net (code "71") (name "P5V0") (class "Default")
      (node (ref "C10") (pin "2") (pinfunction "2_2") (pintype "passive"))
      (node (ref "C11") (pin "2") (pinfunction "2_2") (pintype "passive"))
      (node (ref "C118") (pin "2") (pinfunction "2_2") (pintype "passive"))
      (node (ref "C157") (pin "2") (pinfunction "2_2") (pintype "passive"))
      (node (ref "C158") (pin "2") (pinfunction "2_2") (pintype "passive"))
      (node (ref "C164") (pin "2") (pinfunction "2_2") (pintype "passive"))
      (node (ref "C165") (pin "1") (pinfunction "1_1") (pintype "passive"))
      (node (ref "C78") (pin "2") (pinfunction "2_2") (pintype "passive"))
      (node (ref "C8") (pin "2") (pinfunction "2_2") (pintype "passive"))
      (node (ref "C9") (pin "2") (pinfunction "2_2") (pintype "passive"))
      (node (ref "IC15") (pin "24") (pinfunction "VOUT_24") (pintype "output"))
      (node (ref "IC15") (pin "25") (pinfunction "VOUT_25") (pintype "output"))
      (node (ref "IC15") (pin "26") (pinfunction "VOUT_26") (pintype "output"))
      (node (ref "IC15") (pin "27") (pinfunction "VOUT_27") (pintype "output"))
      (node (ref "IC15") (pin "28") (pinfunction "VOUT_28") (pintype "output"))
      (node (ref "IC15") (pin "29") (pinfunction "VOUT_29") (pintype "output"))
      (node (ref "IC15") (pin "30") (pinfunction "VOUT_30") (pintype "output"))
      (node (ref "IC15") (pin "31") (pinfunction "VOUT_31") (pintype "output"))
      (node (ref "IC15") (pin "32") (pinfunction "VOUT_32") (pintype "output"))
      (node (ref "IC15") (pin "33") (pinfunction "VOUT_33") (pintype "output"))
      (node (ref "IC15") (pin "34") (pinfunction "VOUT_34") (pintype "output"))
      (node (ref "IC15") (pin "35") (pinfunction "VOUT_35") (pintype "output"))
      (node (ref "IC15") (pin "36") (pinfunction "VOUT_36") (pintype "output"))
      (node (ref "IC17") (pin "1") (pinfunction "EN_1") (pintype "input"))
      (node (ref "IC17") (pin "4") (pinfunction "VIN_4") (pintype "input"))
      (node (ref "IC34") (pin "C1") (pinfunction "VOUT_C1") (pintype "power_in"))
      (node (ref "IC34") (pin "D1") (pinfunction "VOUT_D1") (pintype "power_in"))
      (node (ref "IC34") (pin "D2") (pinfunction "VOUT_D2") (pintype "power_in"))
      (node (ref "IC34") (pin "E1") (pinfunction "VOUT_E1") (pintype "power_in"))
      (node (ref "IC34") (pin "E2") (pinfunction "VOUT_E2") (pintype "power_in"))
      (node (ref "IC35") (pin "C1") (pinfunction "VOUT_C1") (pintype "power_in"))
      (node (ref "IC35") (pin "D1") (pinfunction "VOUT_D1") (pintype "power_in"))
      (node (ref "IC35") (pin "D2") (pinfunction "VOUT_D2") (pintype "power_in"))
      (node (ref "IC35") (pin "E1") (pinfunction "VOUT_E1") (pintype "power_in"))
      (node (ref "IC35") (pin "E2") (pinfunction "VOUT_E2") (pintype "power_in"))
      (node (ref "IC37") (pin "C1") (pinfunction "VOUT_C1") (pintype "power_in"))
      (node (ref "IC37") (pin "D1") (pinfunction "VOUT_D1") (pintype "power_in"))
      (node (ref "IC37") (pin "D2") (pinfunction "VOUT_D2") (pintype "power_in"))
      (node (ref "IC37") (pin "E1") (pinfunction "VOUT_E1") (pintype "power_in"))
      (node (ref "IC37") (pin "E2") (pinfunction "VOUT_E2") (pintype "power_in"))
      (node (ref "R100") (pin "1") (pinfunction "1_1") (pintype "passive"))
      (node (ref "R124") (pin "1") (pinfunction "1_1") (pintype "passive"))
      (node (ref "R86") (pin "2") (pinfunction "2_2") (pintype "passive"))
      (node (ref "TP7") (pin "1") (pinfunction "1_1") (pintype "bidirectional"))
    )
    (net (code "72") (name "P5V0A") (class "Default")
      (node (ref "C113") (pin "2") (pinfunction "2_2") (pintype "passive"))
      (node (ref "D25") (pin "1") (pinfunction "C_1") (pintype "passive"))
      (node (ref "IC18") (pin "1") (pinfunction "VOUT_1") (pintype "power_in"))
      (node (ref "IC18") (pin "2") (pinfunction "SENS_2") (pintype "input"))
      (node (ref "R39") (pin "1") (pinfunction "1_1") (pintype "passive"))
      (node (ref "TP11") (pin "1") (pinfunction "1_1") (pintype "bidirectional"))
    )
    (net (code "73") (name "P12V0") (class "Default")
      (node (ref "C101") (pin "2") (pinfunction "2_2") (pintype "passive"))
      (node (ref "C117") (pin "2") (pinfunction "2_2") (pintype "passive"))
      (node (ref "C12") (pin "2") (pinfunction "2_2") (pintype "passive"))
      (node (ref "C13") (pin "2") (pinfunction "2_2") (pintype "passive"))
      (node (ref "C14") (pin "2") (pinfunction "2_2") (pintype "passive"))
      (node (ref "C15") (pin "1") (pinfunction "1_1") (pintype "passive"))
      (node (ref "C155") (pin "2") (pinfunction "2_2") (pintype "passive"))
      (node (ref "C156") (pin "2") (pinfunction "2_2") (pintype "passive"))
      (node (ref "C163") (pin "2") (pinfunction "2_2") (pintype "passive"))
      (node (ref "C166") (pin "2") (pinfunction "2_2") (pintype "passive"))
      (node (ref "C167") (pin "2") (pinfunction "2_2") (pintype "passive"))
      (node (ref "IC15") (pin "12") (pinfunction "PVIN_12") (pintype "input"))
      (node (ref "IC15") (pin "13") (pinfunction "PVIN_13") (pintype "input"))
      (node (ref "IC15") (pin "14") (pinfunction "PVIN_14") (pintype "input"))
      (node (ref "IC15") (pin "15") (pinfunction "PVIN_15") (pintype "input"))
      (node (ref "IC15") (pin "16") (pinfunction "PVIN_16") (pintype "input"))
      (node (ref "IC15") (pin "17") (pinfunction "PVIN_17") (pintype "input"))
      (node (ref "IC15") (pin "18") (pinfunction "PVIN_18") (pintype "input"))
      (node (ref "IC15") (pin "19") (pinfunction "PVIN_19") (pintype "input"))
      (node (ref "IC15") (pin "20") (pinfunction "PVIN_20") (pintype "input"))
      (node (ref "IC15") (pin "21") (pinfunction "PVIN_21") (pintype "input"))
      (node (ref "IC15") (pin "22") (pinfunction "PVIN_22") (pintype "input"))
      (node (ref "IC15") (pin "60") (pinfunction "VIN_60") (pintype "input"))
      (node (ref "IC22") (pin "4") (pinfunction "VIN+_4") (pintype "input"))
      (node (ref "IC34") (pin "A3") (pinfunction "RUN_A3") (pintype "input"))
      (node (ref "IC34") (pin "C5") (pinfunction "SVIN_C5") (pintype "power_in"))
      (node (ref "IC34") (pin "D5") (pinfunction "VIN_D5") (pintype "power_in"))
      (node (ref "IC34") (pin "E5") (pinfunction "VIN_E5") (pintype "power_in"))
      (node (ref "IC35") (pin "A3") (pinfunction "RUN_A3") (pintype "input"))
      (node (ref "IC35") (pin "C5") (pinfunction "SVIN_C5") (pintype "power_in"))
      (node (ref "IC35") (pin "D5") (pinfunction "VIN_D5") (pintype "power_in"))
      (node (ref "IC35") (pin "E5") (pinfunction "VIN_E5") (pintype "power_in"))
      (node (ref "IC37") (pin "A3") (pinfunction "RUN_A3") (pintype "input"))
      (node (ref "IC37") (pin "C5") (pinfunction "SVIN_C5") (pintype "power_in"))
      (node (ref "IC37") (pin "D5") (pinfunction "VIN_D5") (pintype "power_in"))
      (node (ref "IC37") (pin "E5") (pinfunction "VIN_E5") (pintype "power_in"))
      (node (ref "R128") (pin "1") (pinfunction "1_1") (pintype "passive"))
      (node (ref "R13") (pin "2") (pinfunction "2_2") (pintype "passive"))
      (node (ref "R138") (pin "1") (pinfunction "1_1") (pintype "passive"))
      (node (ref "R69") (pin "2") (pinfunction "2_2") (pintype "passive"))
      (node (ref "R88") (pin "1") (pinfunction "1_1") (pintype "passive"))
      (node (ref "R90") (pin "2") (pinfunction "2_2") (pintype "passive"))
      (node (ref "R97") (pin "1") (pinfunction "1_1") (pintype "passive"))
      (node (ref "T7") (pin "2") (pinfunction "S_2") (pintype "passive"))
      (node (ref "TP6") (pin "1") (pinfunction "1_1") (pintype "bidirectional"))
    )
    (net (code "74") (name "P12V0_IN") (class "Default")
      (node (ref "D24") (pin "1") (pinfunction "C_1") (pintype "passive"))
      (node (ref "IC22") (pin "5") (pinfunction "V+_5") (pintype "power_in"))
      (node (ref "J4") (pin "3") (pinfunction "3_3") (pintype "bidirectional"))
      (node (ref "J5") (pin "3") (pinfunction "3_3") (pintype "bidirectional"))
      (node (ref "J5") (pin "4") (pinfunction "4_4") (pintype "bidirectional"))
      (node (ref "R131") (pin "2") (pinfunction "2_2") (pintype "passive"))
      (node (ref "R69") (pin "1") (pinfunction "1_1") (pintype "passive"))
      (node (ref "T3") (pin "1") (pinfunction "S_1") (pintype "passive"))
      (node (ref "T3") (pin "2") (pinfunction "S_2") (pintype "passive"))
      (node (ref "T3") (pin "3") (pinfunction "S_3") (pintype "passive"))
      (node (ref "T5") (pin "1") (pinfunction "E_1") (pintype "passive"))
    )
    (net (code "75") (name "unconnected-(IC3-ADJ-Pad9)") (class "Default")
      (node (ref "IC3") (pin "9") (pinfunction "ADJ_9") (pintype "input+no_connect"))
    )
    (net (code "76") (name "unconnected-(IC12-NC-Pad4)") (class "Default")
      (node (ref "IC12") (pin "4") (pinfunction "NC_4") (pintype "passive+no_connect"))
    )
    (net (code "77") (name "unconnected-(IC15-BST-Pad52)") (class "Default")
      (node (ref "IC15") (pin "52") (pinfunction "BST_52") (pintype "passive+no_connect"))
    )
    (net (code "78") (name "unconnected-(IC15-BST-Pad53)") (class "Default")
      (node (ref "IC15") (pin "53") (pinfunction "BST_53") (pintype "passive+no_connect"))
    )
    (net (code "79") (name "unconnected-(IC15-BST-Pad54)") (class "Default")
      (node (ref "IC15") (pin "54") (pinfunction "BST_54") (pintype "passive+no_connect"))
    )
    (net (code "80") (name "unconnected-(IC15-NC-Pad55)") (class "Default")
      (node (ref "IC15") (pin "55") (pinfunction "NC_55") (pintype "passive+no_connect"))
    )
    (net (code "81") (name "unconnected-(IC15-PG-Pad58)") (class "Default")
      (node (ref "IC15") (pin "58") (pinfunction "PG_58") (pintype "output+no_connect"))
    )
    (net (code "82") (name "unconnected-(IC15-RIA-Pad46)") (class "Default")
      (node (ref "IC15") (pin "46") (pinfunction "RIA_46") (pintype "passive+no_connect"))
    )
    (net (code "83") (name "unconnected-(IC15-RIA-Pad47)") (class "Default")
      (node (ref "IC15") (pin "47") (pinfunction "RIA_47") (pintype "passive+no_connect"))
    )
    (net (code "84") (name "unconnected-(IC16-NC-Pad3)") (class "Default")
      (node (ref "IC16") (pin "3") (pinfunction "NC_3") (pintype "passive+no_connect"))
    )
    (net (code "85") (name "unconnected-(IC16-TRIM-Pad5)") (class "Default")
      (node (ref "IC16") (pin "5") (pinfunction "TRIM_5") (pintype "passive+no_connect"))
    )
    (net (code "86") (name "unconnected-(IC18-NC-Pad4)") (class "Default")
      (node (ref "IC18") (pin "4") (pinfunction "NC_4") (pintype "passive+no_connect"))
    )
    (net (code "87") (name "unconnected-(IC18-PG-Pad7)") (class "Default")
      (node (ref "IC18") (pin "7") (pinfunction "PG_7") (pintype "output+no_connect"))
    )
    (net (code "88") (name "unconnected-(IC34-CLKIN-PadA5)") (class "Default")
      (node (ref "IC34") (pin "A5") (pinfunction "CLKIN_A5") (pintype "input+no_connect"))
    )
    (net (code "89") (name "unconnected-(IC37-CLKOUT-PadB5)") (class "Default")
      (node (ref "IC37") (pin "B5") (pinfunction "CLKOUT_B5") (pintype "output"))
    )
    (net (code "90") (name "unconnected-(IC37-PHMODE-PadB2)") (class "Default")
      (node (ref "IC37") (pin "B2") (pinfunction "PHMODE_B2") (pintype "input+no_connect"))
    )
    (net (code "91") (name "unconnected-(J4-Pad2)") (class "Default")
      (node (ref "J4") (pin "2") (pinfunction "2_2") (pintype "bidirectional"))
    )
  )
)
